# firefly-ice-blue.net
KiCad netlist of a schematic drawn in EAGLE
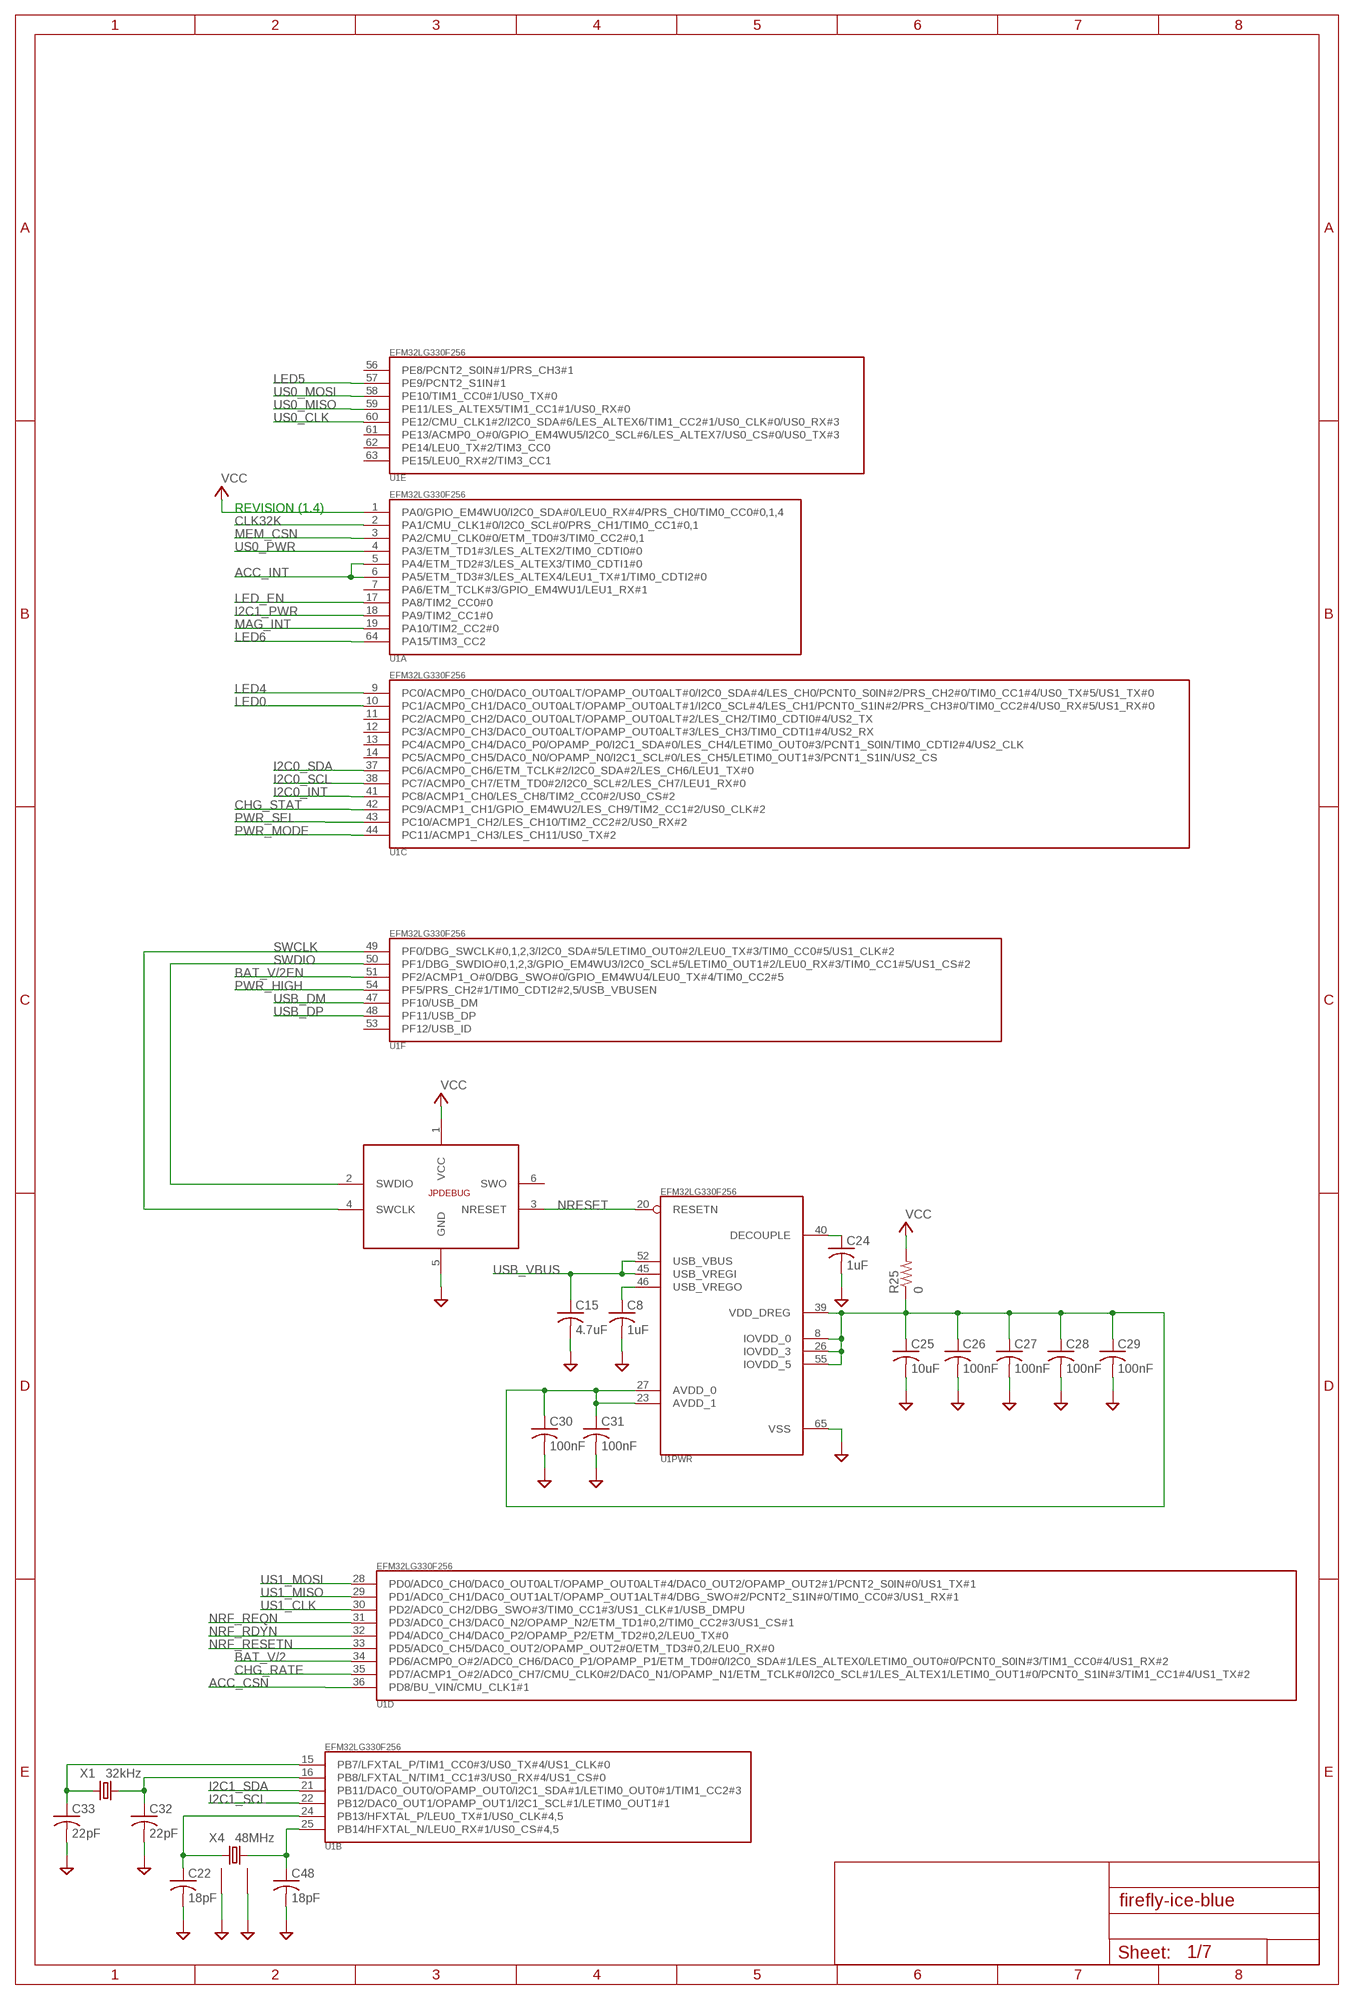
[diagram p0: schematic, sheet 1]
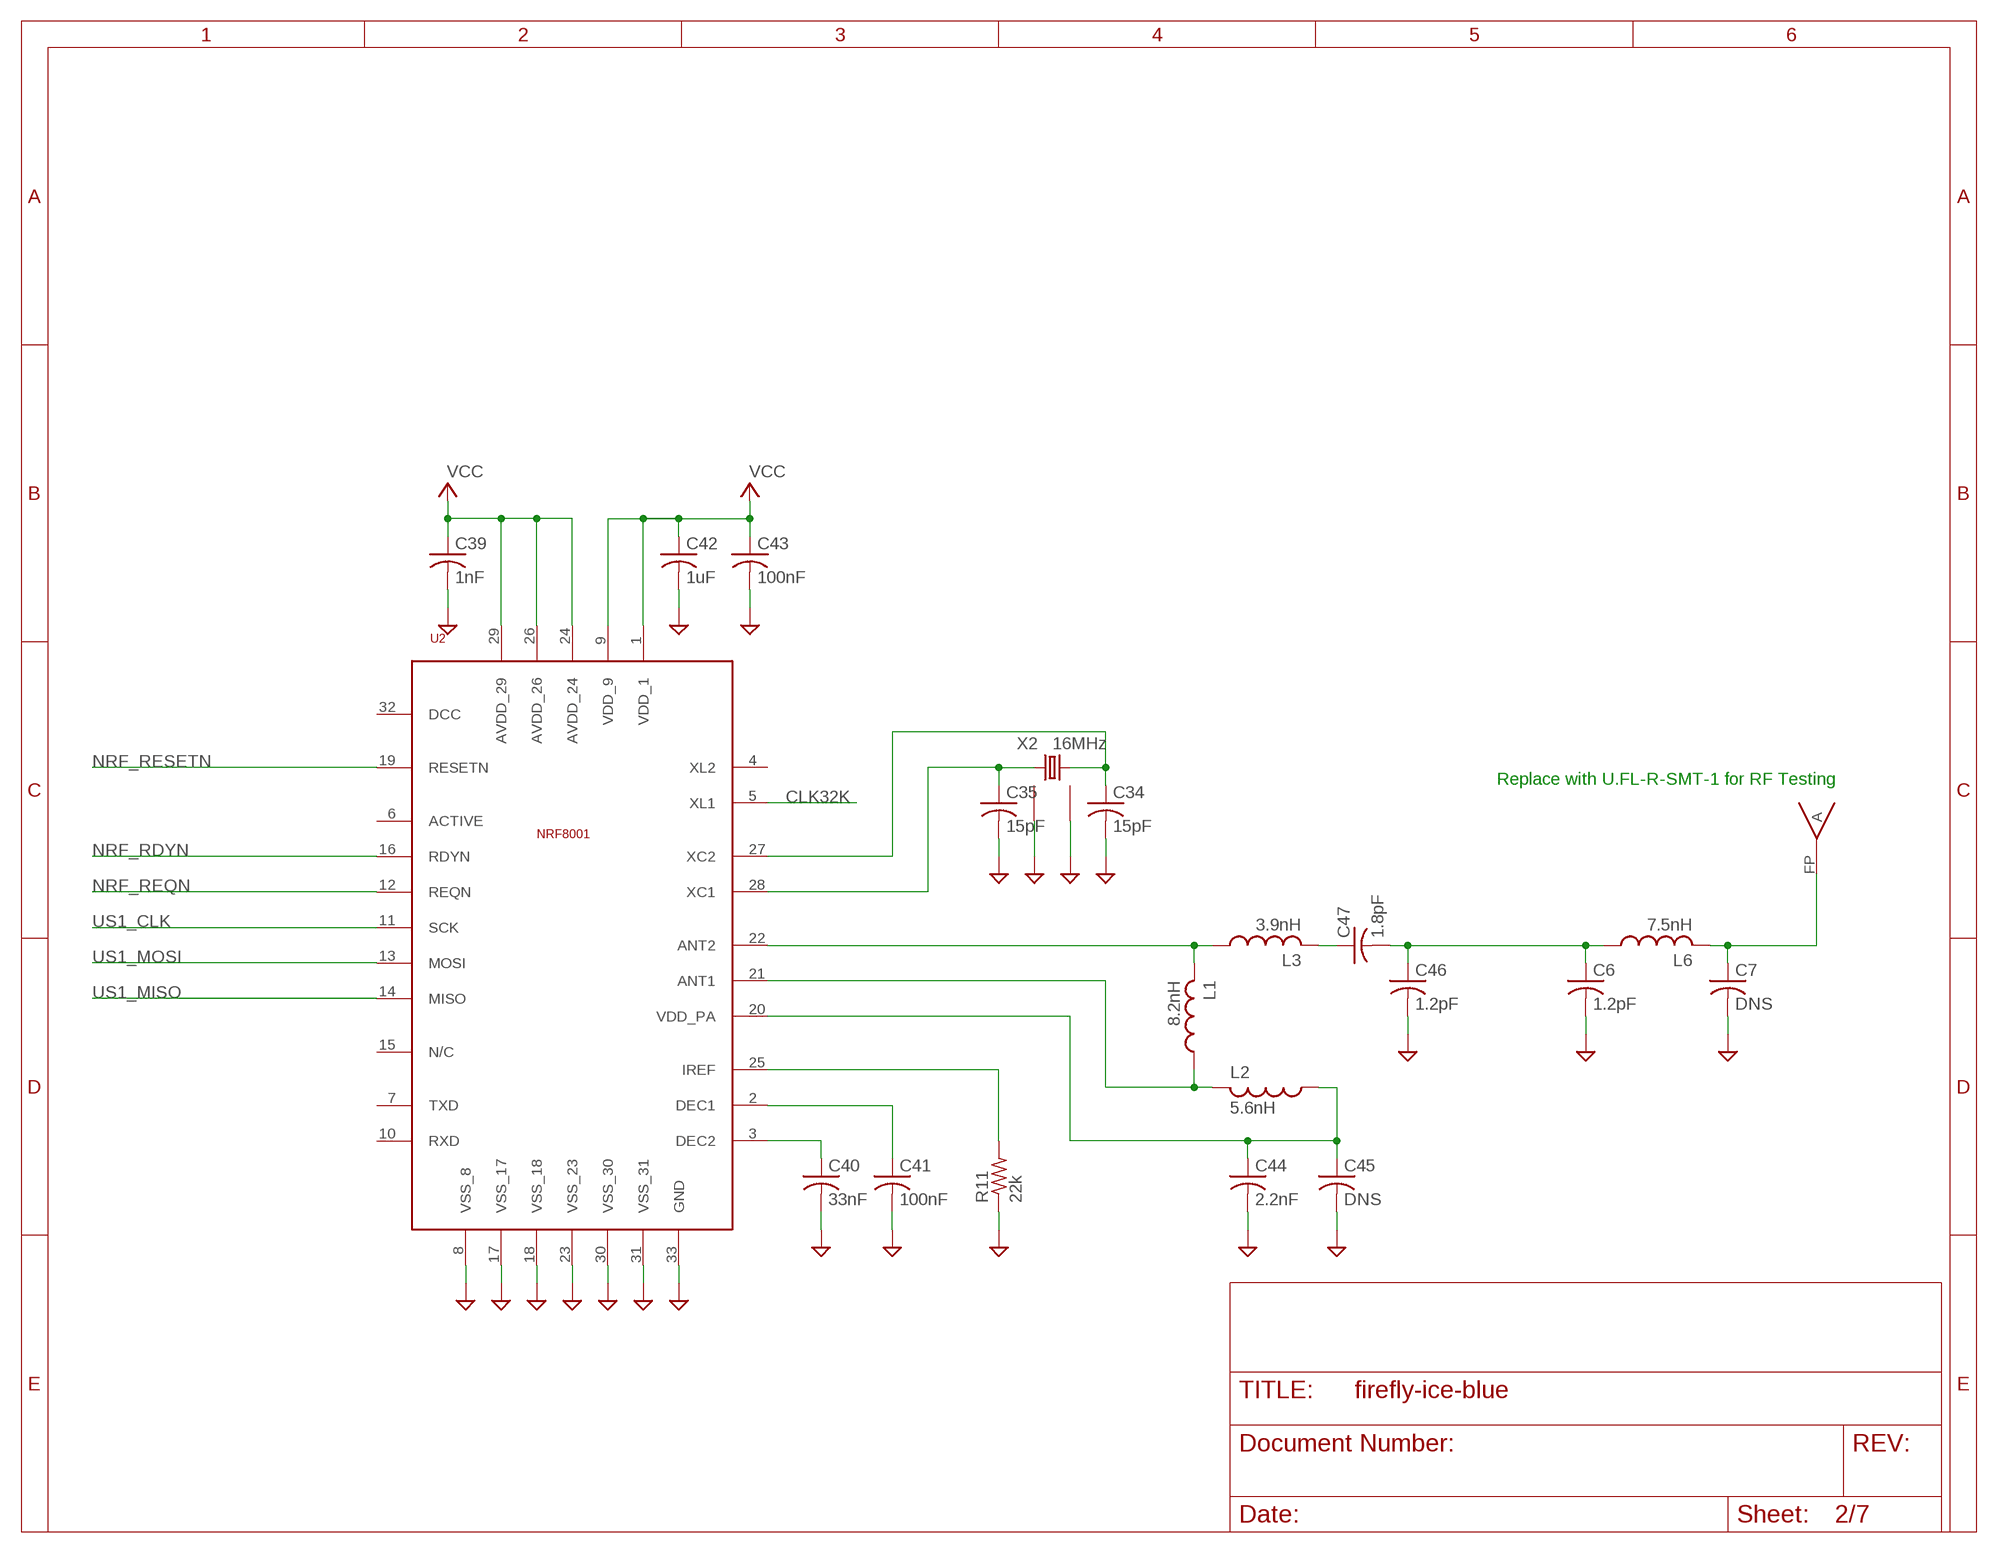
[diagram p1: schematic, sheet 2]
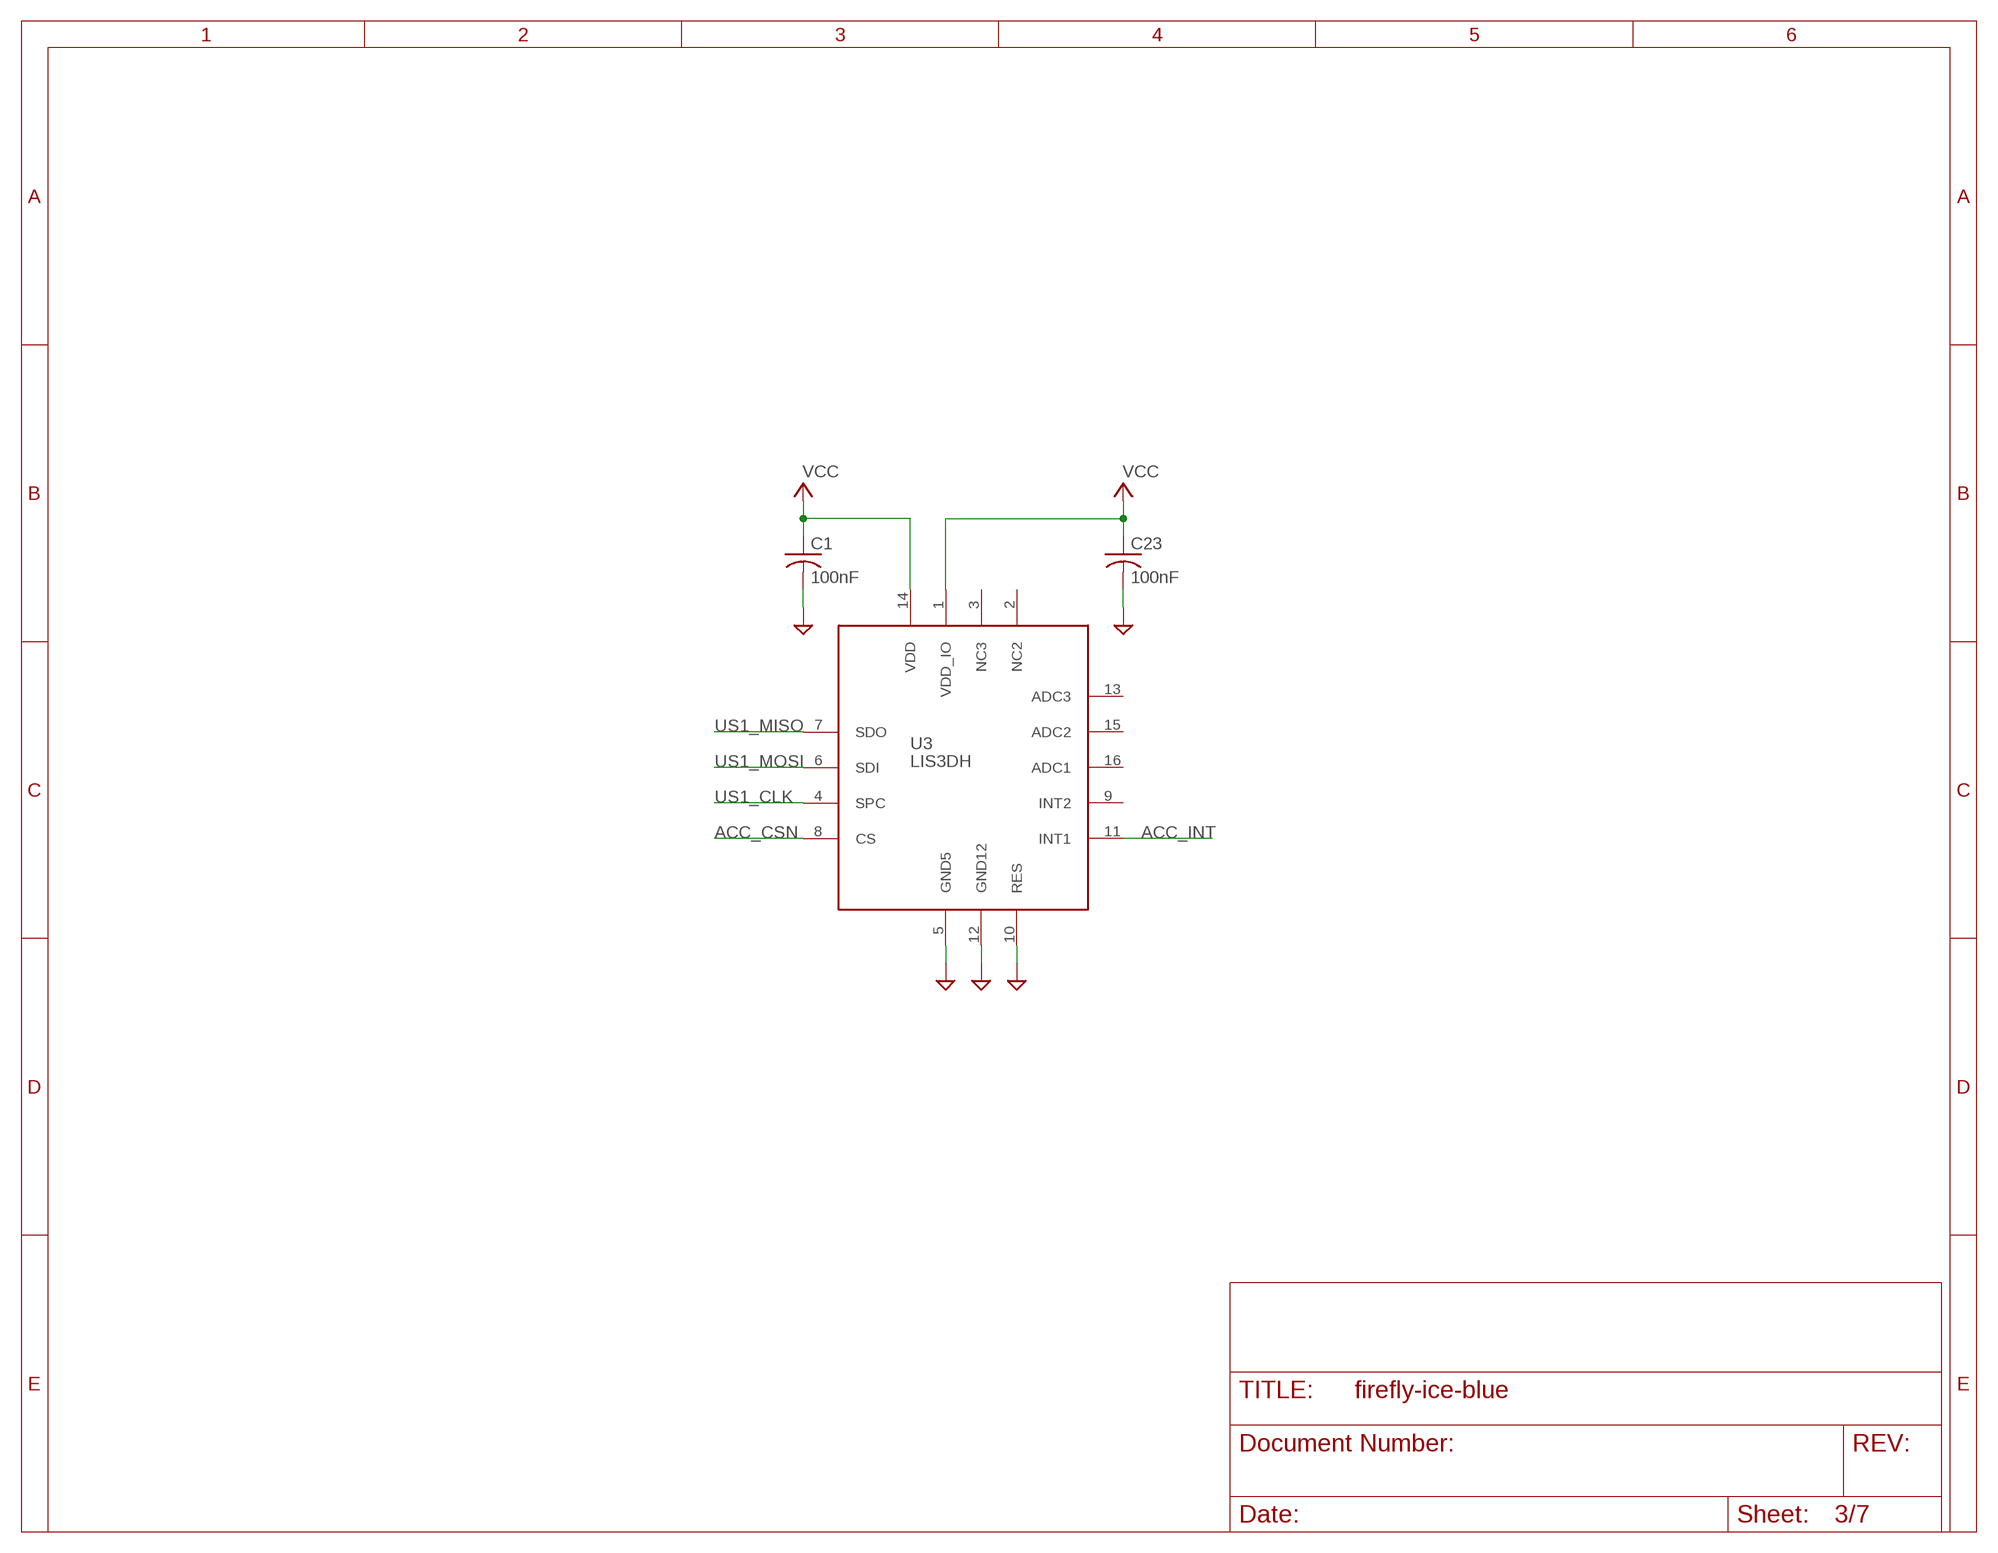
[diagram p2: schematic, sheet 3]
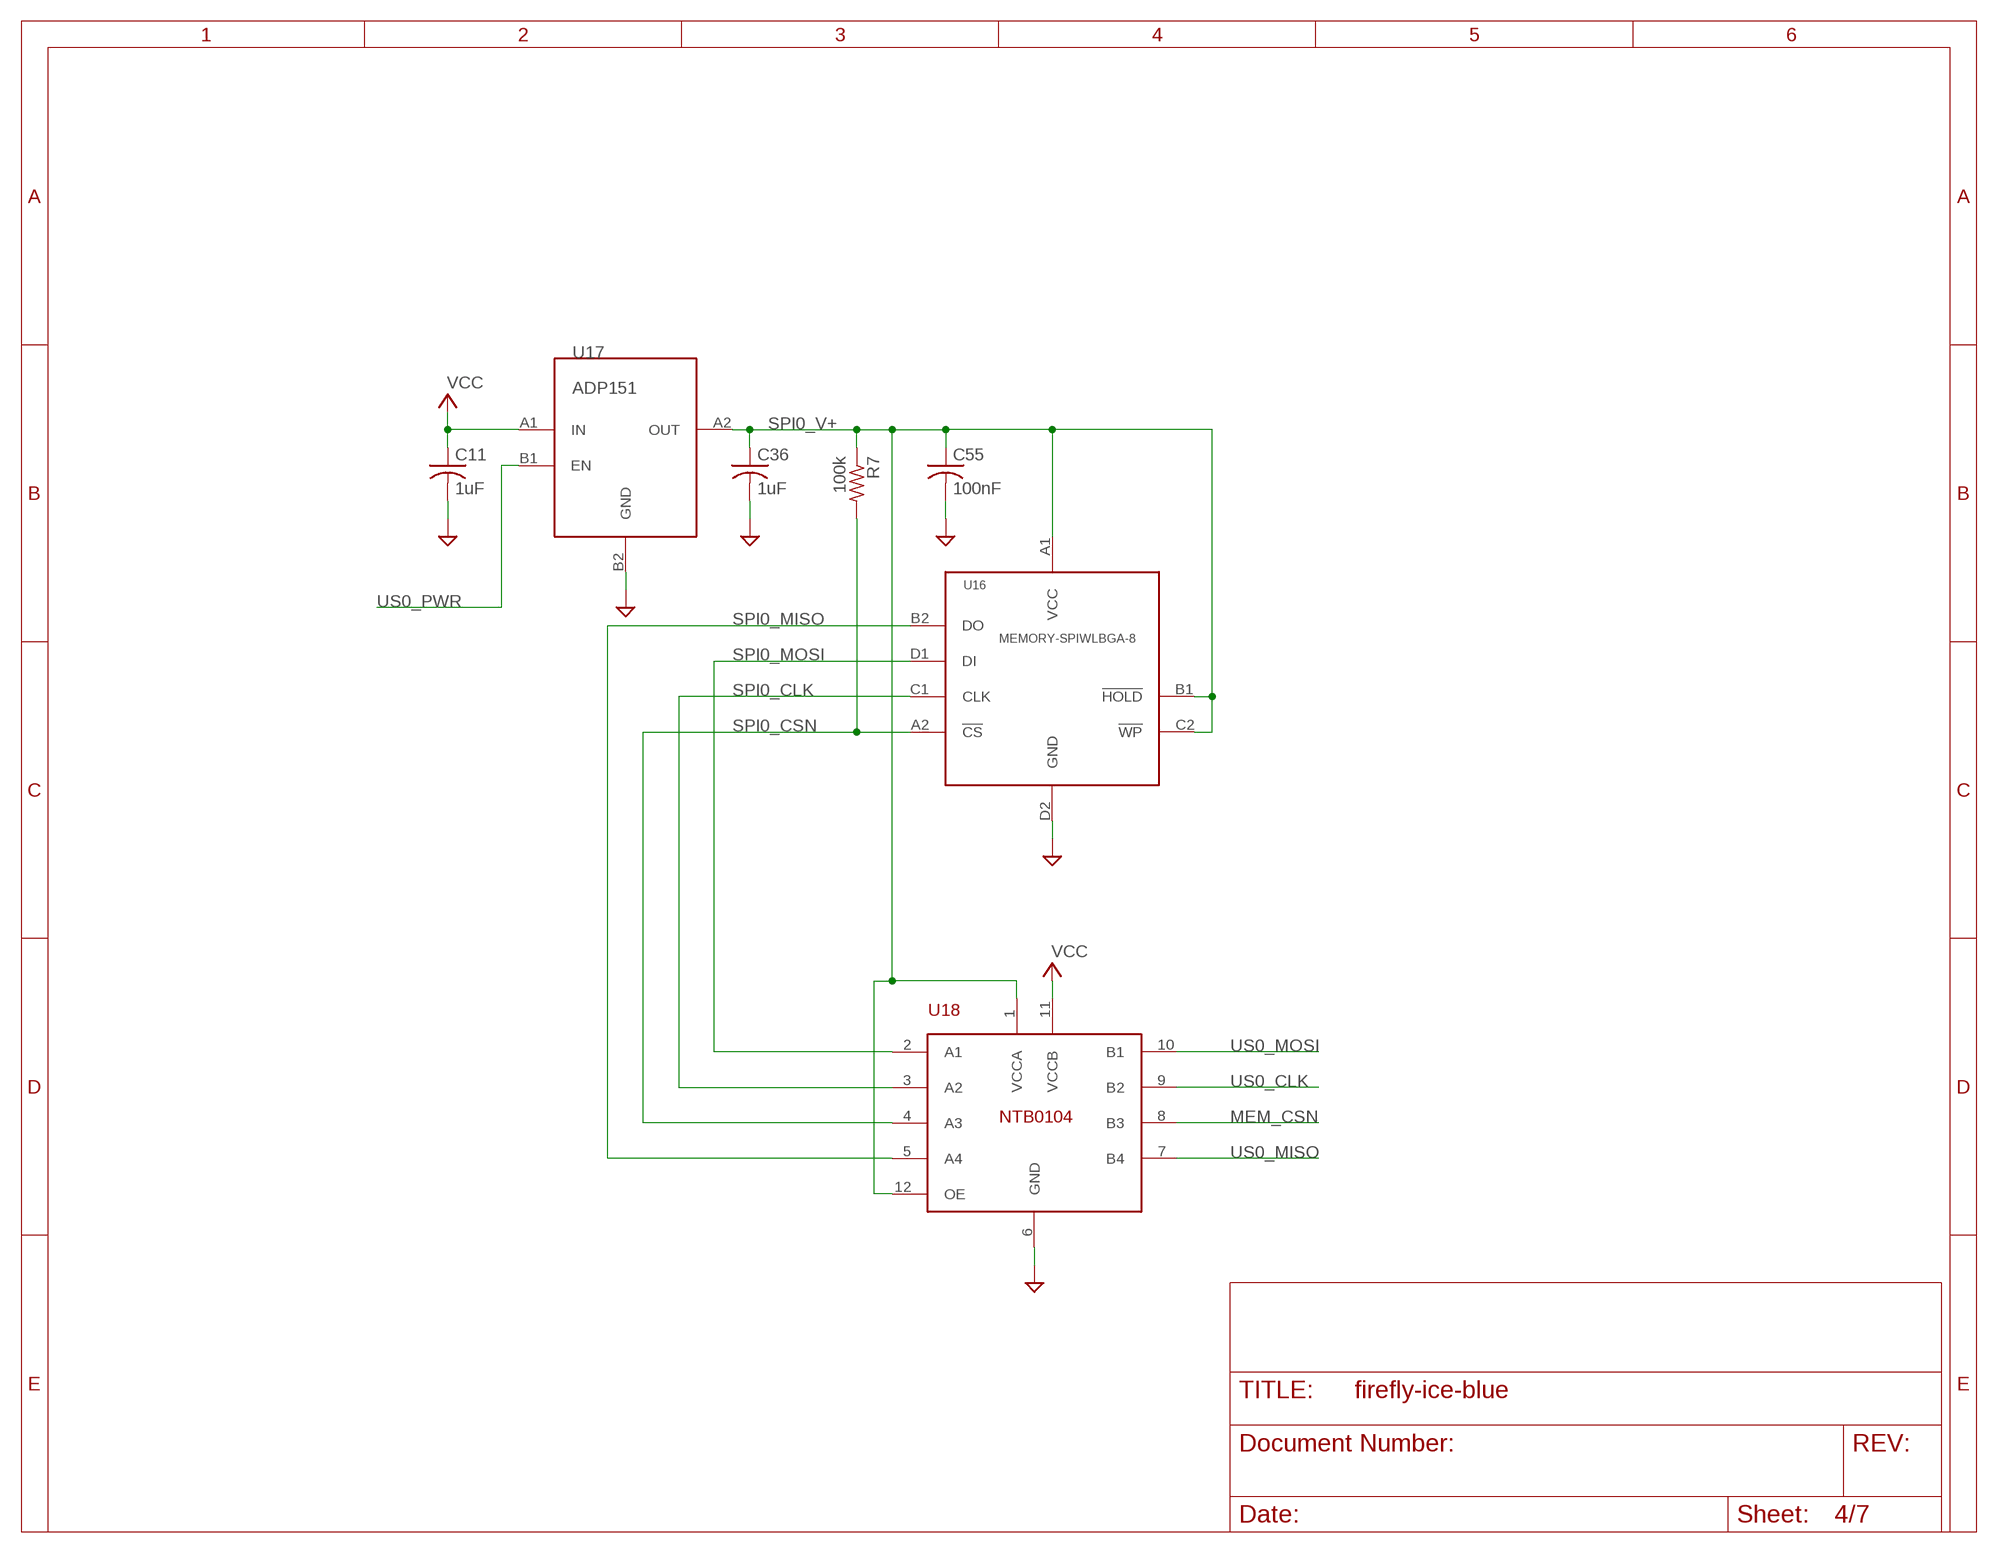
[diagram p3: schematic, sheet 4]
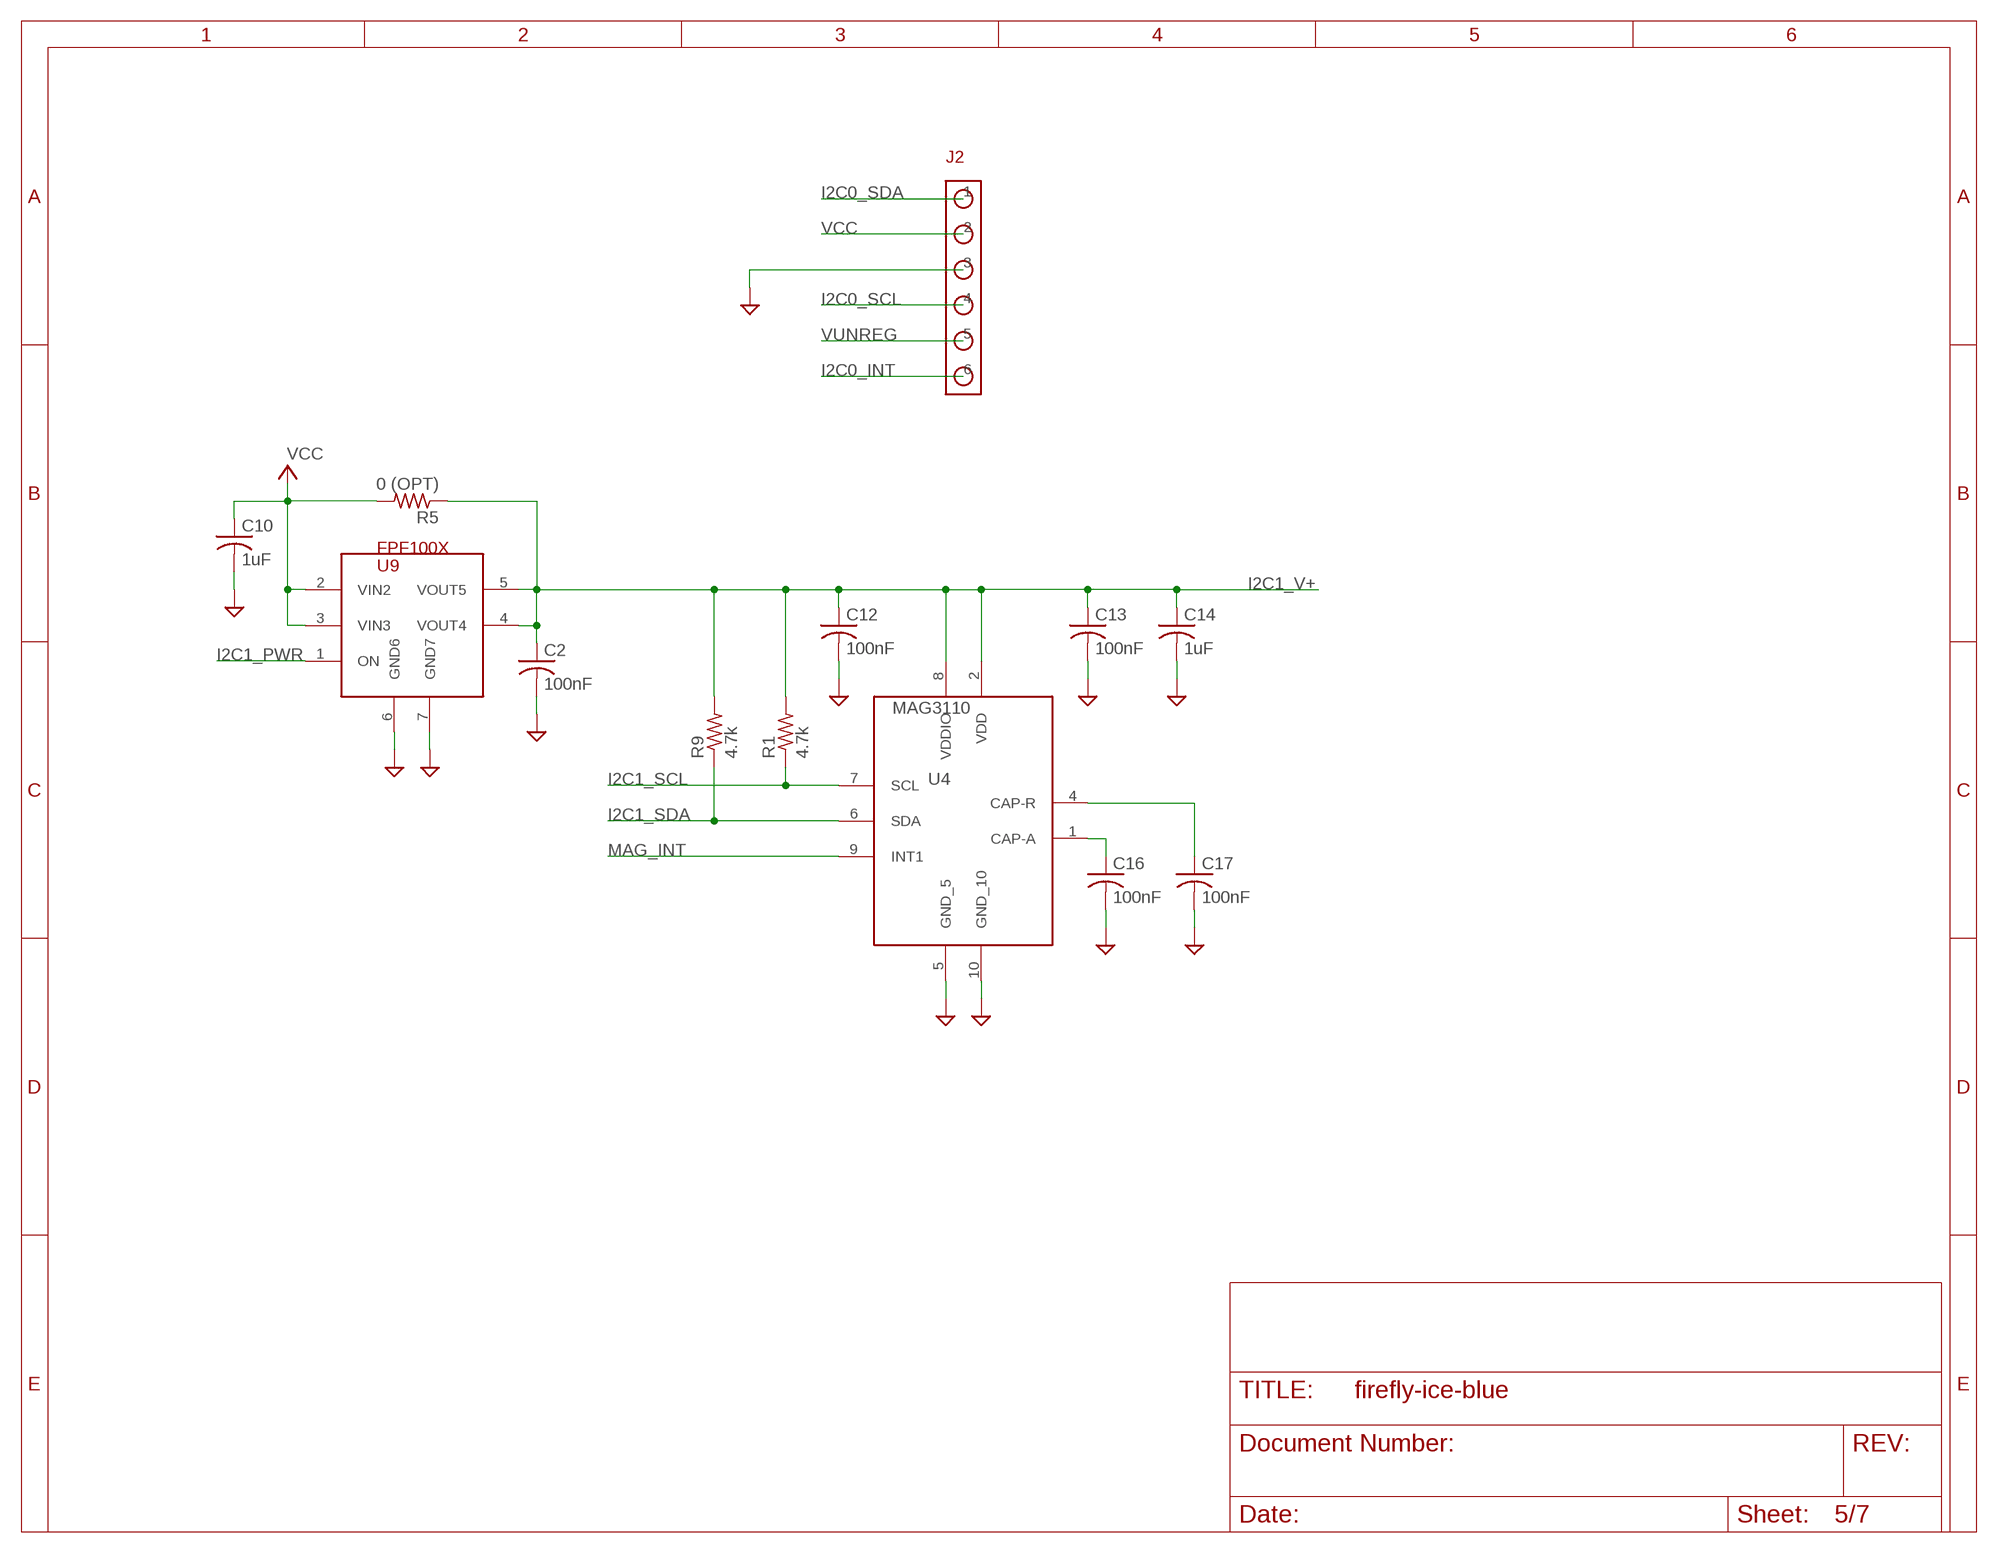
[diagram p4: schematic, sheet 5]
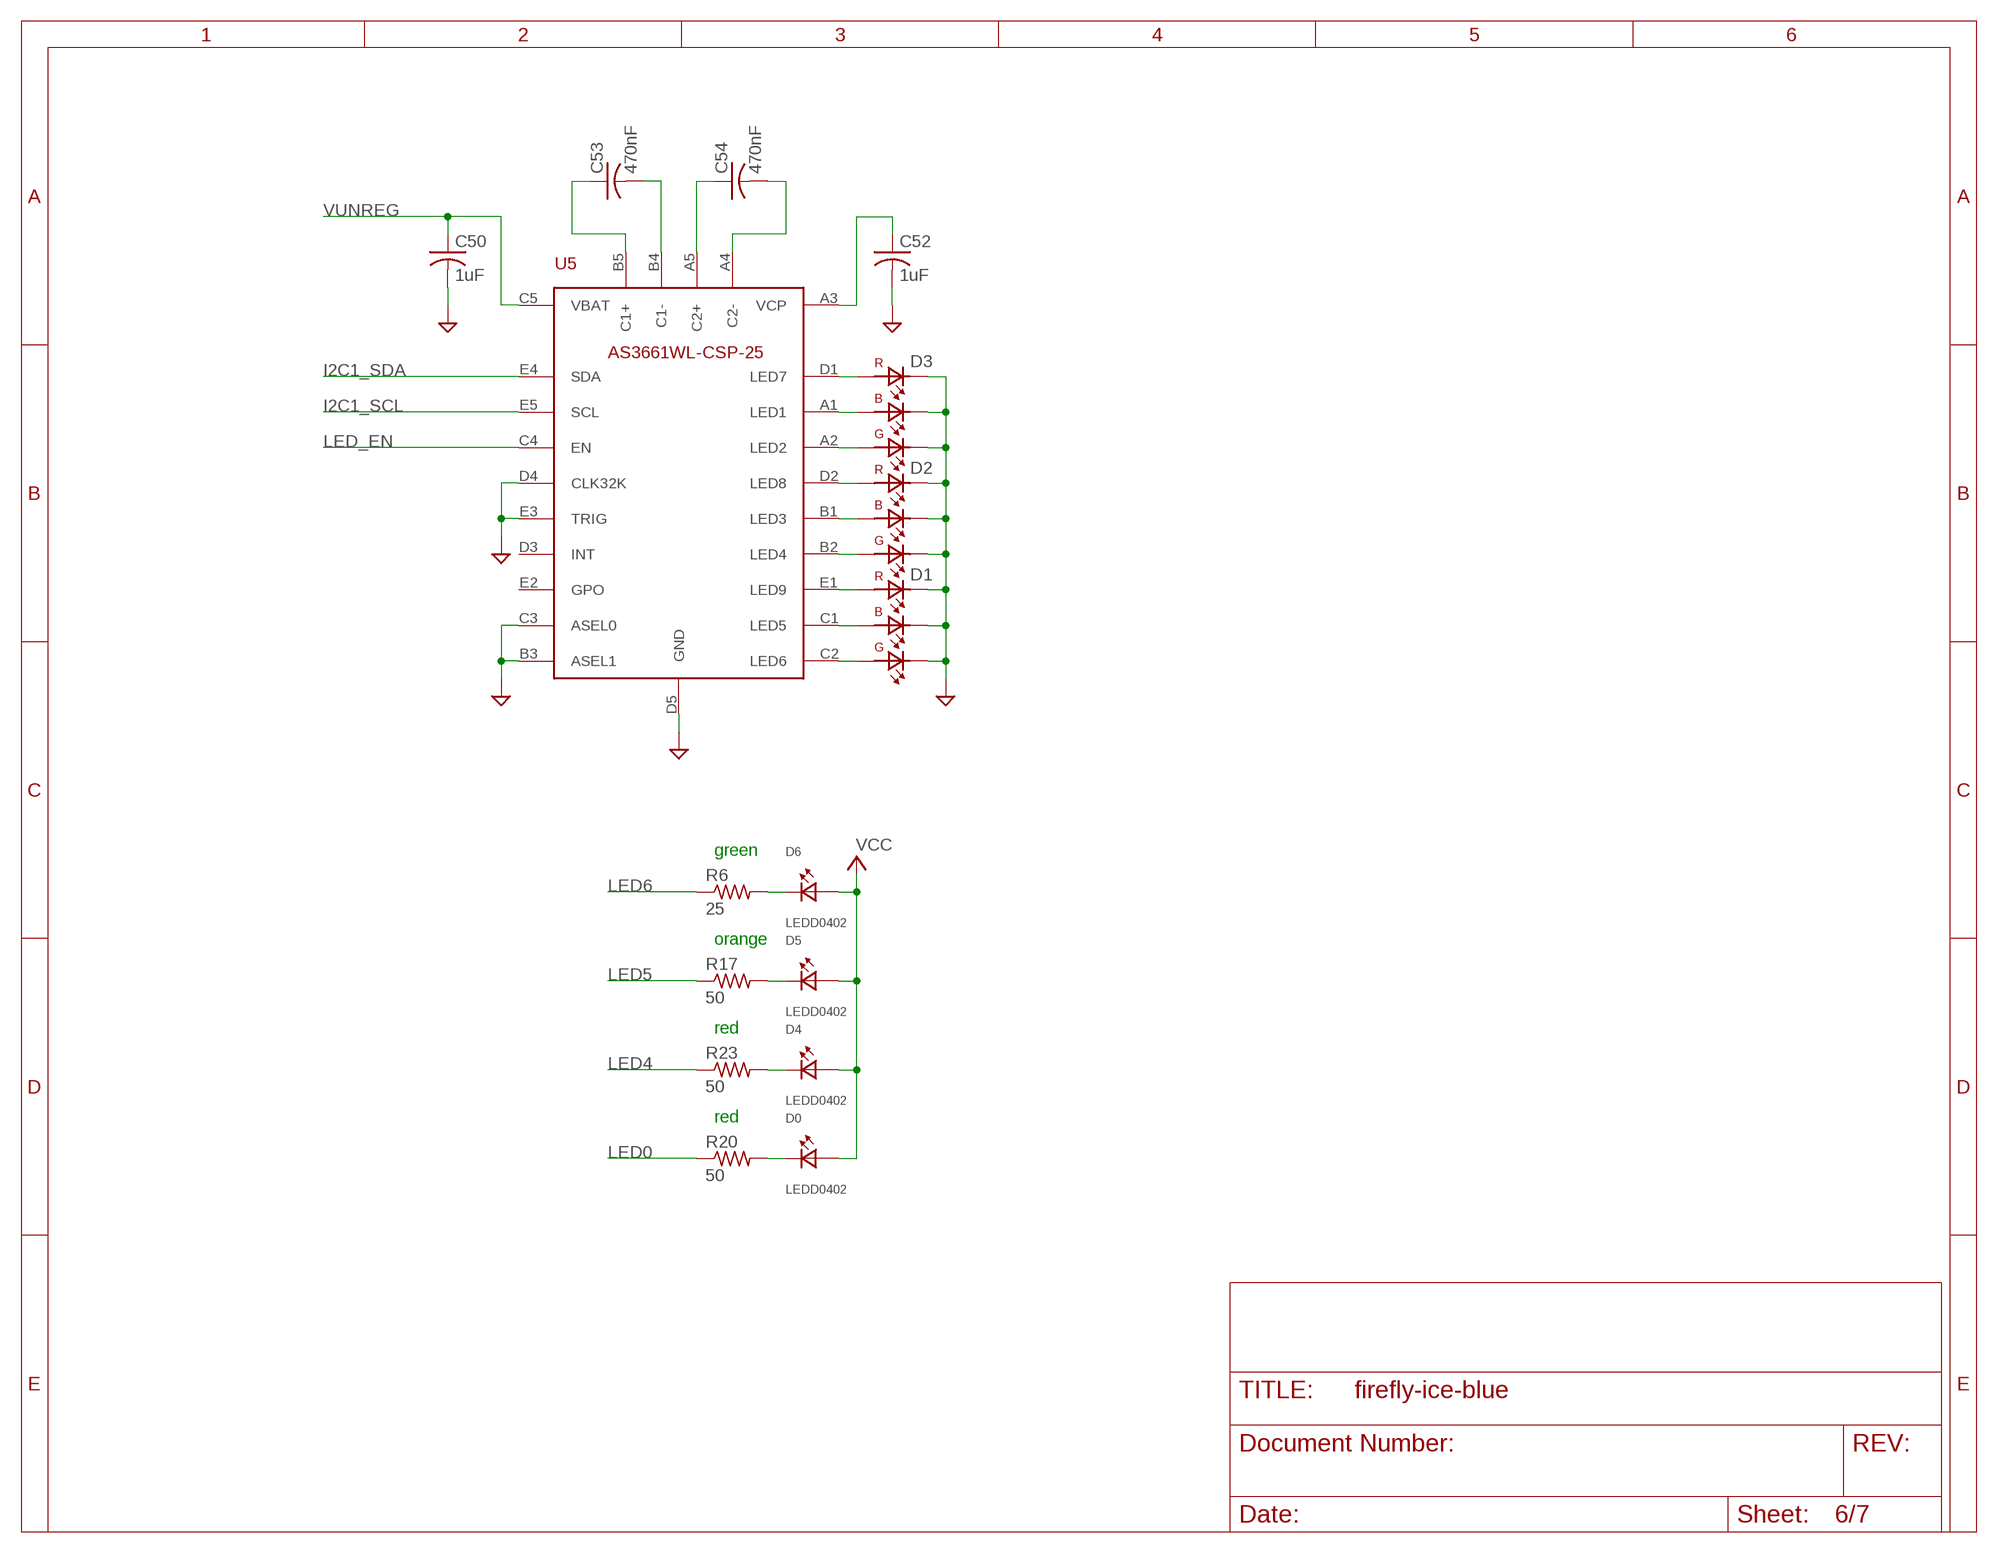
[diagram p5: schematic, sheet 6]
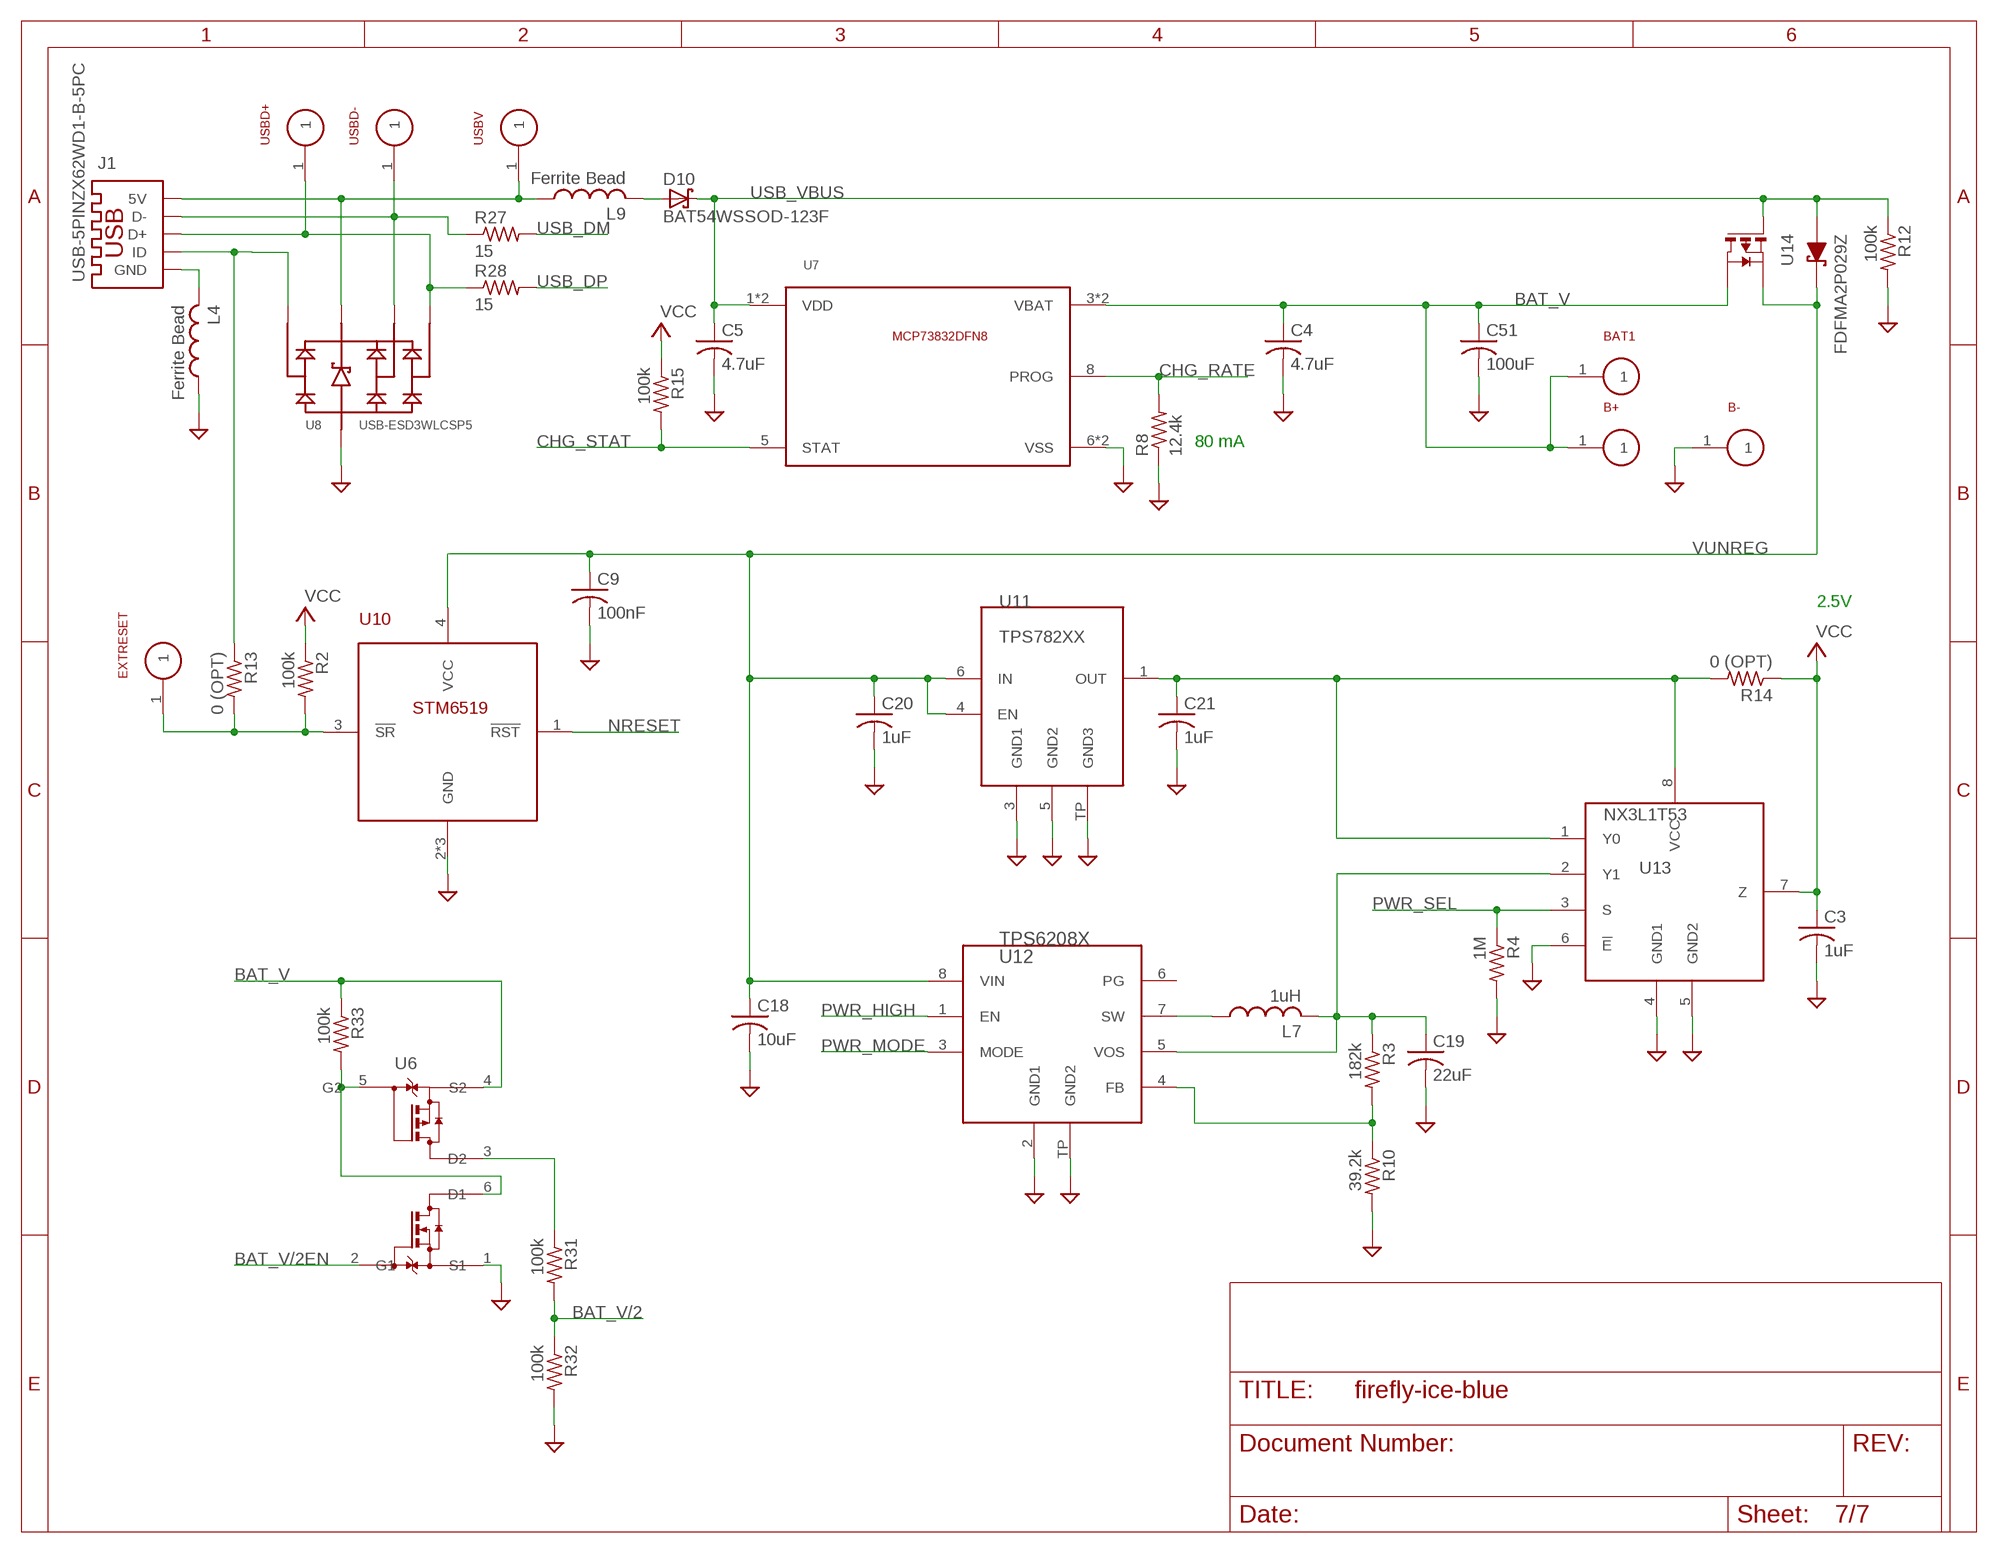
[diagram p6: schematic, sheet 7]

(export (version "E")
  (design (tool "Eeschema 10.0.6"))
  (components
    (comp (ref "C8")
      (value "1uF")
      (footprint "eagle-import:C0201")
      (fields (field (name "MANUFACTURER") "TDK Corporation"))
      (libsource (lib "eagle-import") (part "C-USC0201"))
    )
    (comp (ref "C15")
      (value "4.7uF")
      (footprint "eagle-import:C0402")
      (fields (field (name "MANUFACTURER") "TDK Corporation"))
      (libsource (lib "eagle-import") (part "C-USC0402"))
    )
    (comp (ref "C22")
      (value "18pF")
      (footprint "eagle-import:C0201")
      (fields (field (name "MANUFACTURER") "Johanson Technology Inc"))
      (libsource (lib "eagle-import") (part "C-USC0201"))
    )
    (comp (ref "C24")
      (value "1uF")
      (footprint "eagle-import:C0201")
      (fields (field (name "MANUFACTURER") "TDK Corporation"))
      (libsource (lib "eagle-import") (part "C-USC0201"))
    )
    (comp (ref "C25")
      (value "10uF")
      (footprint "eagle-import:C0402")
      (fields (field (name "MANUFACTURER") "Samsung Electro-Mechanics America, Inc"))
      (libsource (lib "eagle-import") (part "C-USC0402"))
    )
    (comp (ref "C26")
      (value "100nF")
      (footprint "eagle-import:C0201")
      (fields (field (name "MANUFACTURER") "Murata"))
      (libsource (lib "eagle-import") (part "C-USC0201"))
    )
    (comp (ref "C27")
      (value "100nF")
      (footprint "eagle-import:C0201")
      (fields (field (name "MANUFACTURER") "Murata"))
      (libsource (lib "eagle-import") (part "C-USC0201"))
    )
    (comp (ref "C28")
      (value "100nF")
      (footprint "eagle-import:C0201")
      (fields (field (name "MANUFACTURER") "Murata"))
      (libsource (lib "eagle-import") (part "C-USC0201"))
    )
    (comp (ref "C29")
      (value "100nF")
      (footprint "eagle-import:C0201")
      (fields (field (name "MANUFACTURER") "Murata"))
      (libsource (lib "eagle-import") (part "C-USC0201"))
    )
    (comp (ref "C30")
      (value "100nF")
      (footprint "eagle-import:C0201")
      (fields (field (name "MANUFACTURER") "Murata"))
      (libsource (lib "eagle-import") (part "C-USC0201"))
    )
    (comp (ref "C31")
      (value "100nF")
      (footprint "eagle-import:C0201")
      (fields (field (name "MANUFACTURER") "Murata"))
      (libsource (lib "eagle-import") (part "C-USC0201"))
    )
    (comp (ref "C32")
      (value "22pF")
      (footprint "eagle-import:C0201")
      (fields (field (name "MANUFACTURER") "AVX Corporation"))
      (libsource (lib "eagle-import") (part "C-USC0201"))
    )
    (comp (ref "C33")
      (value "22pF")
      (footprint "eagle-import:C0201")
      (fields (field (name "MANUFACTURER") "AVX Corporation"))
      (libsource (lib "eagle-import") (part "C-USC0201"))
    )
    (comp (ref "C48")
      (value "18pF")
      (footprint "eagle-import:C0201")
      (fields (field (name "MANUFACTURER") "Johanson Technology Inc"))
      (libsource (lib "eagle-import") (part "C-USC0201"))
    )
    (comp (ref "JPDEBUG")
      (value "TC2030-SWD")
      (footprint "eagle-import:TC2030-MCP-NL")
      (libsource (lib "eagle-import") (part "TC2030-SWD"))
    )
    (comp (ref "R25")
      (value "0")
      (footprint "eagle-import:R0201")
      (fields (field (name "MANUFACTURER") "Panasonic Electronic Components"))
      (libsource (lib "eagle-import") (part "R-US_R0201"))
    )
    (comp (ref "U1")
      (value "EFM32LG330F256")
      (footprint "eagle-import:QFN64")
      (fields
        (field (name "MANUFACTURER") "Energy Micro")
        (field (name "ORDERING-CODE") "EFM32LG330F256-QFN64")
      )
      (libsource (lib "eagle-import") (part "EFM32LG330F256"))
    )
    (comp (ref "X1")
      (value "32kHz")
      (footprint "eagle-import:9HT10")
      (fields (field (name "MANUFACTURER") "AVX Corp/Kyocera Corp"))
      (libsource (lib "eagle-import") (part "XTAL29HT10"))
    )
    (comp (ref "X4")
      (value "48MHz")
      (footprint "eagle-import:ABM11")
      (fields (field (name "MANUFACTURER") "Abracon Corporation"))
      (libsource (lib "eagle-import") (part "XTALABM11"))
    )
    (comp (ref "C11")
      (value "1uF")
      (footprint "eagle-import:C0201")
      (fields (field (name "MANUFACTURER") "TDK Corporation"))
      (libsource (lib "eagle-import") (part "C-USC0201"))
    )
    (comp (ref "C36")
      (value "1uF")
      (footprint "eagle-import:C0201")
      (fields (field (name "MANUFACTURER") "TDK Corporation"))
      (libsource (lib "eagle-import") (part "C-USC0201"))
    )
    (comp (ref "C55")
      (value "100nF")
      (footprint "eagle-import:C0201")
      (fields (field (name "MANUFACTURER") "Murata"))
      (libsource (lib "eagle-import") (part "C-USC0201"))
    )
    (comp (ref "R7")
      (value "100k")
      (footprint "eagle-import:R0201")
      (fields (field (name "MANUFACTURER") "Yageo"))
      (libsource (lib "eagle-import") (part "R-US_R0201"))
    )
    (comp (ref "U16")
      (value "MEMORY-SPIWLBGA-8")
      (footprint "eagle-import:WLBGA-8")
      (fields (field (name "MANUFACTURER") "Winbond"))
      (libsource (lib "eagle-import") (part "MEMORY-SPIWLBGA-8"))
    )
    (comp (ref "U17")
      (value "ADP151")
      (footprint "eagle-import:CB-4-3")
      (fields (field (name "MANUFACTURER") "Analog Devices"))
      (libsource (lib "eagle-import") (part "ADP151"))
    )
    (comp (ref "U18")
      (value "NTB0104")
      (footprint "eagle-import:XQFN12")
      (fields (field (name "MANUFACTURER") "NXP Semiconductors"))
      (libsource (lib "eagle-import") (part "NTB0104"))
    )
    (comp (ref "C2")
      (value "100nF")
      (footprint "eagle-import:C0201")
      (fields (field (name "MANUFACTURER") "Murata"))
      (libsource (lib "eagle-import") (part "C-USC0201"))
    )
    (comp (ref "C10")
      (value "1uF")
      (footprint "eagle-import:C0201")
      (fields (field (name "MANUFACTURER") "TDK Corporation"))
      (libsource (lib "eagle-import") (part "C-USC0201"))
    )
    (comp (ref "C12")
      (value "100nF")
      (footprint "eagle-import:C0201")
      (fields (field (name "MANUFACTURER") "Murata"))
      (libsource (lib "eagle-import") (part "C-USC0201"))
    )
    (comp (ref "C13")
      (value "100nF")
      (footprint "eagle-import:C0201")
      (fields (field (name "MANUFACTURER") "Murata"))
      (libsource (lib "eagle-import") (part "C-USC0201"))
    )
    (comp (ref "C14")
      (value "1uF")
      (footprint "eagle-import:C0201")
      (fields (field (name "MANUFACTURER") "TDK Corporation"))
      (libsource (lib "eagle-import") (part "C-USC0201"))
    )
    (comp (ref "C16")
      (value "100nF")
      (footprint "eagle-import:C0201")
      (fields (field (name "MANUFACTURER") "Murata"))
      (libsource (lib "eagle-import") (part "C-USC0201"))
    )
    (comp (ref "C17")
      (value "100nF")
      (footprint "eagle-import:C0201")
      (fields (field (name "MANUFACTURER") "Murata"))
      (libsource (lib "eagle-import") (part "C-USC0201"))
    )
    (comp (ref "J2")
      (value "CON-6SOCKET")
      (footprint "eagle-import:M40-3100345R")
      (fields (field (name "MANUFACTURER") "Harwin Inc"))
      (libsource (lib "eagle-import") (part "CON-6SOCKET"))
    )
    (comp (ref "R1")
      (value "4.7k")
      (footprint "eagle-import:R0201")
      (fields (field (name "MANUFACTURER") "Panasonic Electronic Components"))
      (libsource (lib "eagle-import") (part "R-US_R0201"))
    )
    (comp (ref "R5")
      (value "0 (OPT)")
      (footprint "eagle-import:R0201")
      (fields (field (name "MANUFACTURER") "Panasonic Electronic Components"))
      (libsource (lib "eagle-import") (part "R-US_R0201"))
    )
    (comp (ref "R9")
      (value "4.7k")
      (footprint "eagle-import:R0201")
      (fields (field (name "MANUFACTURER") "Panasonic Electronic Components"))
      (libsource (lib "eagle-import") (part "R-US_R0201"))
    )
    (comp (ref "U4")
      (value "MAG3110")
      (footprint "eagle-import:DFN10-2X2")
      (fields (field (name "MANUFACTURER") "Freescale Semiconductor"))
      (libsource (lib "eagle-import") (part "MAG3110"))
    )
    (comp (ref "U9")
      (value "FPF100X")
      (footprint "eagle-import:MICROFET-2X2-6L")
      (fields (field (name "MANUFACTURER") "Fairchild Semiconductor"))
      (libsource (lib "eagle-import") (part "FPF100X"))
    )
    (comp (ref "B+")
      (value "TARGET-PINWP-28AWG")
      (footprint "eagle-import:WP-28AWG")
      (libsource (lib "eagle-import") (part "TARGET-PINWP-28AWG"))
    )
    (comp (ref "B-")
      (value "TARGET-PINWP-28AWG")
      (footprint "eagle-import:WP-28AWG")
      (libsource (lib "eagle-import") (part "TARGET-PINWP-28AWG"))
    )
    (comp (ref "BAT1")
      (value "TARGET-PIN")
      (footprint "eagle-import:TARGET-PIN-1MM")
      (libsource (lib "eagle-import") (part "TARGET-PIN"))
    )
    (comp (ref "C3")
      (value "1uF")
      (footprint "eagle-import:C0201")
      (fields (field (name "MANUFACTURER") "TDK Corporation"))
      (libsource (lib "eagle-import") (part "C-USC0201"))
    )
    (comp (ref "C4")
      (value "4.7uF")
      (footprint "eagle-import:C0402")
      (fields (field (name "MANUFACTURER") "TDK Corporation"))
      (libsource (lib "eagle-import") (part "C-USC0402"))
    )
    (comp (ref "C5")
      (value "4.7uF")
      (footprint "eagle-import:C0402")
      (fields (field (name "MANUFACTURER") "TDK Corporation"))
      (libsource (lib "eagle-import") (part "C-USC0402"))
    )
    (comp (ref "C9")
      (value "100nF")
      (footprint "eagle-import:C0201")
      (fields (field (name "MANUFACTURER") "Murata"))
      (libsource (lib "eagle-import") (part "C-USC0201"))
    )
    (comp (ref "C18")
      (value "10uF")
      (footprint "eagle-import:C0402")
      (fields (field (name "MANUFACTURER") "Samsung Electro-Mechanics America, Inc"))
      (libsource (lib "eagle-import") (part "C-USC0402"))
    )
    (comp (ref "C19")
      (value "22uF")
      (footprint "eagle-import:C0603")
      (fields (field (name "MANUFACTURER") "TDK Corporation"))
      (libsource (lib "eagle-import") (part "C-USC0603"))
    )
    (comp (ref "C20")
      (value "1uF")
      (footprint "eagle-import:C0201")
      (fields (field (name "MANUFACTURER") "TDK Corporation"))
      (libsource (lib "eagle-import") (part "C-USC0201"))
    )
    (comp (ref "C21")
      (value "1uF")
      (footprint "eagle-import:C0201")
      (fields (field (name "MANUFACTURER") "TDK Corporation"))
      (libsource (lib "eagle-import") (part "C-USC0201"))
    )
    (comp (ref "C51")
      (value "100uF")
      (footprint "eagle-import:C1206")
      (fields (field (name "MANUFACTURER") "Kemet"))
      (libsource (lib "eagle-import") (part "C-USC1206"))
    )
    (comp (ref "D10")
      (value "BAT54WSSOD-123F")
      (footprint "eagle-import:SOD-123F")
      (fields (field (name "MANUFACTURER") "Rohm Semiconductor"))
      (libsource (lib "eagle-import") (part "BAT54WSSOD-123F"))
    )
    (comp (ref "EXTRESET")
      (value "TARGET-PIN")
      (footprint "eagle-import:TARGET-PIN-1MM")
      (libsource (lib "eagle-import") (part "TARGET-PIN"))
    )
    (comp (ref "J1")
      (value "USB-5PINZX62WD1-B-5PC")
      (footprint "eagle-import:ZX62WD1-B-5PC")
      (fields (field (name "MANUFACTURER") "TE Connectivity"))
      (libsource (lib "eagle-import") (part "USB-5PINZX62WD1-B-5PC"))
    )
    (comp (ref "L4")
      (value "Ferrite Bead")
      (footprint "eagle-import:L0201")
      (fields (field (name "MANUFACTURER") "TDK Corporation"))
      (libsource (lib "eagle-import") (part "L-USL0201"))
    )
    (comp (ref "L7")
      (value "1uH")
      (footprint "eagle-import:L0805")
      (fields (field (name "MANUFACTURER") "WURTH"))
      (libsource (lib "eagle-import") (part "INDUCTORL0805"))
    )
    (comp (ref "L9")
      (value "Ferrite Bead")
      (footprint "eagle-import:L0201")
      (fields (field (name "MANUFACTURER") "TDK Corportation"))
      (libsource (lib "eagle-import") (part "L-USL0201"))
    )
    (comp (ref "R2")
      (value "100k")
      (footprint "eagle-import:R0201")
      (fields (field (name "MANUFACTURER") "Yageo"))
      (libsource (lib "eagle-import") (part "R-US_R0201"))
    )
    (comp (ref "R3")
      (value "182k")
      (footprint "eagle-import:R0201")
      (fields (field (name "MANUFACTURER") "Panasonic Electronic Components"))
      (libsource (lib "eagle-import") (part "R-US_R0201"))
    )
    (comp (ref "R4")
      (value "1M")
      (footprint "eagle-import:R0201")
      (fields (field (name "MANUFACTURER") "Panasonic Electronic Components"))
      (libsource (lib "eagle-import") (part "R-US_R0201"))
    )
    (comp (ref "R8")
      (value "12.4k")
      (footprint "eagle-import:R0201")
      (fields (field (name "MANUFACTURER") "Panasonic Electronic Components"))
      (libsource (lib "eagle-import") (part "R-US_R0201"))
    )
    (comp (ref "R10")
      (value "39.2k")
      (footprint "eagle-import:R0201")
      (fields (field (name "MANUFACTURER") "Panasonic Electronic Components"))
      (libsource (lib "eagle-import") (part "R-US_R0201"))
    )
    (comp (ref "R12")
      (value "100k")
      (footprint "eagle-import:R0201")
      (fields (field (name "MANUFACTURER") "Yageo"))
      (libsource (lib "eagle-import") (part "R-US_R0201"))
    )
    (comp (ref "R13")
      (value "0 (OPT)")
      (footprint "eagle-import:R0201")
      (fields (field (name "MANUFACTURER") "Panasonic Electronic Components"))
      (libsource (lib "eagle-import") (part "R-US_R0201"))
    )
    (comp (ref "R14")
      (value "0 (OPT)")
      (footprint "eagle-import:R0201")
      (fields (field (name "MANUFACTURER") "Panasonic Electronic Components"))
      (libsource (lib "eagle-import") (part "R-US_R0201"))
    )
    (comp (ref "R15")
      (value "100k")
      (footprint "eagle-import:R0201")
      (fields (field (name "MANUFACTURER") "Yageo"))
      (libsource (lib "eagle-import") (part "R-US_R0201"))
    )
    (comp (ref "R27")
      (value "15")
      (footprint "eagle-import:R0201")
      (fields (field (name "MANUFACTURER") "Panasonic Electronic Components"))
      (libsource (lib "eagle-import") (part "R-US_R0201"))
    )
    (comp (ref "R28")
      (value "15")
      (footprint "eagle-import:R0201")
      (fields (field (name "MANUFACTURER") "Panasonic Electronic Components"))
      (libsource (lib "eagle-import") (part "R-US_R0201"))
    )
    (comp (ref "R31")
      (value "100k")
      (footprint "eagle-import:R0201")
      (fields (field (name "MANUFACTURER") "Yageo"))
      (libsource (lib "eagle-import") (part "R-US_R0201"))
    )
    (comp (ref "R32")
      (value "100k")
      (footprint "eagle-import:R0201")
      (fields (field (name "MANUFACTURER") "Yageo"))
      (libsource (lib "eagle-import") (part "R-US_R0201"))
    )
    (comp (ref "R33")
      (value "100k")
      (footprint "eagle-import:R0201")
      (fields (field (name "MANUFACTURER") "Yageo"))
      (libsource (lib "eagle-import") (part "R-US_R0201"))
    )
    (comp (ref "U6")
      (value "MOSFET-N+PSOT963")
      (footprint "eagle-import:SOT963")
      (fields (field (name "MANUFACTURER") "Diodes Inc"))
      (libsource (lib "eagle-import") (part "MOSFET-N+PSOT963"))
    )
    (comp (ref "U7")
      (value "MCP73832DFN8")
      (footprint "eagle-import:DFN8")
      (fields (field (name "MANUFACTURER") "Microchip"))
      (libsource (lib "eagle-import") (part "MCP73832DFN8"))
    )
    (comp (ref "U8")
      (value "USB-ESD3WLCSP5")
      (footprint "eagle-import:WLCSP5")
      (fields (field (name "MANUFACTURER") "NXP Semiconductors"))
      (libsource (lib "eagle-import") (part "USB-ESD3WLCSP5"))
    )
    (comp (ref "U10")
      (value "STM6519")
      (footprint "eagle-import:UDFN6")
      (fields (field (name "MANUFACTURER") "STMicroelectronics"))
      (libsource (lib "eagle-import") (part "STM6519"))
    )
    (comp (ref "U11")
      (value "TPS782XX")
      (footprint "eagle-import:S-PWSON-N6")
      (fields (field (name "MANUFACTURER") "Texas Instruments"))
      (libsource (lib "eagle-import") (part "TPS782XX"))
    )
    (comp (ref "U12")
      (value "TPS6208X")
      (footprint "eagle-import:S-PWSON-N8")
      (fields (field (name "MANUFACTURER") "Texas Instruments"))
      (libsource (lib "eagle-import") (part "TPS6208X"))
    )
    (comp (ref "U13")
      (value "NX3L1T53")
      (footprint "eagle-import:SOT902-2")
      (fields (field (name "MANUFACTURER") "NXP Semiconductor"))
      (libsource (lib "eagle-import") (part "NX3L1T53"))
    )
    (comp (ref "U14")
      (value "FDFMA2P029Z")
      (footprint "eagle-import:MO-229")
      (fields (field (name "MANUFACTURER") "Fairchild Semiconductor"))
      (libsource (lib "eagle-import") (part "FDFMA2P029Z"))
    )
    (comp (ref "USBD+")
      (value "TARGET-PIN")
      (footprint "eagle-import:TARGET-PIN-1MM")
      (libsource (lib "eagle-import") (part "TARGET-PIN"))
    )
    (comp (ref "USBD-")
      (value "TARGET-PIN")
      (footprint "eagle-import:TARGET-PIN-1MM")
      (libsource (lib "eagle-import") (part "TARGET-PIN"))
    )
    (comp (ref "USBV")
      (value "TARGET-PIN")
      (footprint "eagle-import:TARGET-PIN-1MM")
      (libsource (lib "eagle-import") (part "TARGET-PIN"))
    )
    (comp (ref "C1")
      (value "100nF")
      (footprint "eagle-import:C0201")
      (fields (field (name "MANUFACTURER") "Murata"))
      (libsource (lib "eagle-import") (part "C-USC0201"))
    )
    (comp (ref "C23")
      (value "100nF")
      (footprint "eagle-import:C0201")
      (fields (field (name "MANUFACTURER") "Murata"))
      (libsource (lib "eagle-import") (part "C-USC0201"))
    )
    (comp (ref "U3")
      (value "LIS3DH")
      (footprint "eagle-import:LGA16_3X3")
      (fields (field (name "MANUFACTURER") "ST"))
      (libsource (lib "eagle-import") (part "LIS3DH"))
    )
    (comp (ref "A1")
      (value "FR05_S1_N_0_110")
      (footprint "eagle-import:FR05_S1_N_0_110")
      (fields (field (name "MANUFACTURER") "Fractus"))
      (libsource (lib "eagle-import") (part "FR05_S1_N_0_110"))
    )
    (comp (ref "C6")
      (value "1.2pF")
      (footprint "eagle-import:C0201")
      (fields (field (name "MANUFACTURER") "TDK"))
      (libsource (lib "eagle-import") (part "C-USC0201"))
    )
    (comp (ref "C7")
      (value "DNS")
      (footprint "eagle-import:C0201")
      (libsource (lib "eagle-import") (part "C-USC0201"))
    )
    (comp (ref "C34")
      (value "15pF")
      (footprint "eagle-import:C0201")
      (fields (field (name "MANUFACTURER") "Johanson Technology Inc"))
      (libsource (lib "eagle-import") (part "C-USC0201"))
    )
    (comp (ref "C35")
      (value "15pF")
      (footprint "eagle-import:C0201")
      (fields (field (name "MANUFACTURER") "Johanson Technology Inc"))
      (libsource (lib "eagle-import") (part "C-USC0201"))
    )
    (comp (ref "C39")
      (value "1nF")
      (footprint "eagle-import:C0201")
      (fields (field (name "MANUFACTURER") "Murata"))
      (libsource (lib "eagle-import") (part "C-USC0201"))
    )
    (comp (ref "C40")
      (value "33nF")
      (footprint "eagle-import:C0201")
      (fields (field (name "MANUFACTURER") "Murata"))
      (libsource (lib "eagle-import") (part "C-USC0201"))
    )
    (comp (ref "C41")
      (value "100nF")
      (footprint "eagle-import:C0201")
      (fields (field (name "MANUFACTURER") "Kemet"))
      (libsource (lib "eagle-import") (part "C-USC0201"))
    )
    (comp (ref "C42")
      (value "1uF")
      (footprint "eagle-import:C0201")
      (fields (field (name "MANUFACTURER") "TDK Corporation"))
      (libsource (lib "eagle-import") (part "C-USC0201"))
    )
    (comp (ref "C43")
      (value "100nF")
      (footprint "eagle-import:C0201")
      (fields (field (name "MANUFACTURER") "Murata"))
      (libsource (lib "eagle-import") (part "C-USC0201"))
    )
    (comp (ref "C44")
      (value "2.2nF")
      (footprint "eagle-import:C0201")
      (fields (field (name "MANUFACTURER") "TDK"))
      (libsource (lib "eagle-import") (part "C-USC0201"))
    )
    (comp (ref "C45")
      (value "DNS")
      (footprint "eagle-import:C0201")
      (libsource (lib "eagle-import") (part "C-USC0201"))
    )
    (comp (ref "C46")
      (value "1.2pF")
      (footprint "eagle-import:C0201")
      (fields (field (name "MANUFACTURER") "TDK"))
      (libsource (lib "eagle-import") (part "C-USC0201"))
    )
    (comp (ref "C47")
      (value "1.8pF")
      (footprint "eagle-import:C0201")
      (fields (field (name "MANUFACTURER") "TDK"))
      (libsource (lib "eagle-import") (part "C-USC0201"))
    )
    (comp (ref "L1")
      (value "8.2nH")
      (footprint "eagle-import:L0201")
      (fields (field (name "MANUFACTURER") "TDK"))
      (libsource (lib "eagle-import") (part "L-USL0201"))
    )
    (comp (ref "L2")
      (value "5.6nH")
      (footprint "eagle-import:L0201")
      (fields (field (name "MANUFACTURER") "TDK"))
      (libsource (lib "eagle-import") (part "L-USL0201"))
    )
    (comp (ref "L3")
      (value "3.9nH")
      (footprint "eagle-import:L0201")
      (fields (field (name "MANUFACTURER") "TDK"))
      (libsource (lib "eagle-import") (part "L-USL0201"))
    )
    (comp (ref "L6")
      (value "7.5nH")
      (footprint "eagle-import:L0201")
      (fields (field (name "MANUFACTURER") "Taiyo Yuden"))
      (libsource (lib "eagle-import") (part "L-USL0201"))
    )
    (comp (ref "R11")
      (value "22k")
      (footprint "eagle-import:R0201")
      (fields (field (name "MANUFACTURER") "Panasonic"))
      (libsource (lib "eagle-import") (part "R-US_R0201"))
    )
    (comp (ref "U2")
      (value "NRF8001")
      (footprint "eagle-import:QFN-32")
      (fields (field (name "MANUFACTURER") "Nordic Semiconductor"))
      (libsource (lib "eagle-import") (part "NRF8001"))
    )
    (comp (ref "X2")
      (value "16MHz")
      (footprint "eagle-import:XTAL2520")
      (fields (field (name "MANUFACTURER") "TXC CORPORATION"))
      (libsource (lib "eagle-import") (part "XTALXTAL2520"))
    )
    (comp (ref "C50")
      (value "1uF")
      (footprint "eagle-import:C0201")
      (fields (field (name "MANUFACTURER") "TDK Corporation"))
      (libsource (lib "eagle-import") (part "C-USC0201"))
    )
    (comp (ref "C52")
      (value "1uF")
      (footprint "eagle-import:C0201")
      (fields (field (name "MANUFACTURER") "TDK Corporation"))
      (libsource (lib "eagle-import") (part "C-USC0201"))
    )
    (comp (ref "C53")
      (value "470nF")
      (footprint "eagle-import:C0201")
      (fields (field (name "MANUFACTURER") "TDK Corporation"))
      (libsource (lib "eagle-import") (part "C-USC0201"))
    )
    (comp (ref "C54")
      (value "470nF")
      (footprint "eagle-import:C0201")
      (fields (field (name "MANUFACTURER") "TDK Corporation"))
      (libsource (lib "eagle-import") (part "C-USC0201"))
    )
    (comp (ref "D0")
      (value "LEDD0402")
      (footprint "eagle-import:D0402")
      (fields (field (name "MANUFACTURER") "Rohm Semiconductor"))
      (libsource (lib "eagle-import") (part "LEDD0402"))
    )
    (comp (ref "D1")
      (value "LED-RGB")
      (footprint "eagle-import:SMLP36")
      (fields (field (name "MANUFACTURER") "Rohm Semiconductor"))
      (libsource (lib "eagle-import") (part "LED-RGB"))
    )
    (comp (ref "D2")
      (value "LED-RGB")
      (footprint "eagle-import:SMLP36")
      (fields (field (name "MANUFACTURER") "Rohm Semiconductor"))
      (libsource (lib "eagle-import") (part "LED-RGB"))
    )
    (comp (ref "D3")
      (value "LED-RGB")
      (footprint "eagle-import:SMLP36")
      (fields (field (name "MANUFACTURER") "Rohm Semiconductor"))
      (libsource (lib "eagle-import") (part "LED-RGB"))
    )
    (comp (ref "D4")
      (value "LEDD0402")
      (footprint "eagle-import:D0402")
      (fields (field (name "MANUFACTURER") "Rohm Semiconductor"))
      (libsource (lib "eagle-import") (part "LEDD0402"))
    )
    (comp (ref "D5")
      (value "LEDD0402")
      (footprint "eagle-import:D0402")
      (fields (field (name "MANUFACTURER") "Panasonic Electronic Components"))
      (libsource (lib "eagle-import") (part "LEDD0402"))
    )
    (comp (ref "D6")
      (value "LEDD0402")
      (footprint "eagle-import:D0402")
      (fields (field (name "MANUFACTURER") "Panasonic Electronic Components"))
      (libsource (lib "eagle-import") (part "LEDD0402"))
    )
    (comp (ref "R6")
      (value "25")
      (footprint "eagle-import:R0201")
      (fields (field (name "MANUFACTURER") "Panasonic Electronic Components"))
      (libsource (lib "eagle-import") (part "R-US_R0201"))
    )
    (comp (ref "R17")
      (value "50")
      (footprint "eagle-import:R0201")
      (fields (field (name "MANUFACTURER") "Panasonic Electronic Components"))
      (libsource (lib "eagle-import") (part "R-US_R0201"))
    )
    (comp (ref "R20")
      (value "50")
      (footprint "eagle-import:R0201")
      (fields (field (name "MANUFACTURER") "Panasonic Electronic Components"))
      (libsource (lib "eagle-import") (part "R-US_R0201"))
    )
    (comp (ref "R23")
      (value "50")
      (footprint "eagle-import:R0201")
      (fields (field (name "MANUFACTURER") "Panasonic Electronic Components"))
      (libsource (lib "eagle-import") (part "R-US_R0201"))
    )
    (comp (ref "U5")
      (value "AS3661WL-CSP-25")
      (footprint "eagle-import:WL-CSP-25")
      (fields (field (name "MANUFACTURER") "Texas Instruments"))
      (libsource (lib "eagle-import") (part "AS3661WL-CSP-25"))
    )
  )
  (nets
    (net (code "1") (name "ACC_CSN") (class "Default")
      (node (ref "U1") (pin "36") (pinfunction "PD8/BU_VIN/CMU_CLK1#1_36") (pintype "bidirectional"))
      (node (ref "U3") (pin "8") (pinfunction "CS_8") (pintype "bidirectional"))
    )
    (net (code "2") (name "ACC_INT") (class "Default")
      (node (ref "U1") (pin "5") (pinfunction "PA4/ETM_TD2#3/LES_ALTEX3/TIM0_CDTI1#0_5") (pintype "bidirectional"))
      (node (ref "U1") (pin "6") (pinfunction "PA5/ETM_TD3#3/LES_ALTEX4/LEU1_TX#1/TIM0_CDTI2#0_6") (pintype "bidirectional"))
      (node (ref "U3") (pin "11") (pinfunction "INT1_11") (pintype "bidirectional"))
    )
    (net (code "3") (name "BAT_V") (class "Default")
      (node (ref "B+") (pin "1") (pinfunction "1_1") (pintype "bidirectional"))
      (node (ref "BAT1") (pin "1") (pinfunction "1_1") (pintype "bidirectional"))
      (node (ref "C4") (pin "1") (pinfunction "1_1") (pintype "passive"))
      (node (ref "C51") (pin "1") (pinfunction "1_1") (pintype "passive"))
      (node (ref "R33") (pin "1") (pinfunction "1_1") (pintype "passive"))
      (node (ref "U14") (pin "3") (pinfunction "D_3") (pintype "passive"))
      (node (ref "U6") (pin "4") (pinfunction "S2_4") (pintype "passive"))
      (node (ref "U7") (pin "3") (pinfunction "VBAT_3") (pintype "bidirectional"))
      (node (ref "U7") (pin "4") (pinfunction "VBAT_4") (pintype "bidirectional"))
    )
    (net (code "4") (name "BAT_V{slash}2") (class "Default")
      (node (ref "R31") (pin "2") (pinfunction "2_2") (pintype "passive"))
      (node (ref "R32") (pin "1") (pinfunction "1_1") (pintype "passive"))
      (node (ref "U1") (pin "34") (pinfunction "PD6/ACMP0_O#2/ADC0_CH6/DAC0_P1/OPAMP_P1/ETM_TD0#0/I2C0_SDA#1/LES_ALTEX0/LETIM0_OUT0#0/PCNT0_S0IN#3/TIM1_CC0#4/US1_RX#2_34") (pintype "bidirectional"))
    )
    (net (code "5") (name "BAT_V{slash}2EN") (class "Default")
      (node (ref "U1") (pin "51") (pinfunction "PF2/ACMP1_O#0/DBG_SWO#0/GPIO_EM4WU4/LEU0_TX#4/TIM0_CC2#5_51") (pintype "bidirectional"))
      (node (ref "U6") (pin "2") (pinfunction "G1_2") (pintype "passive"))
    )
    (net (code "6") (name "CHG_RATE") (class "Default")
      (node (ref "R8") (pin "2") (pinfunction "2_2") (pintype "passive"))
      (node (ref "U1") (pin "35") (pinfunction "PD7/ACMP1_O#2/ADC0_CH7/CMU_CLK0#2/DAC0_N1/OPAMP_N1/ETM_TCLK#0/I2C0_SCL#1/LES_ALTEX1/LETIM0_OUT1#0/PCNT0_S1IN#3/TIM1_CC1#4/US1_TX#2_35") (pintype "bidirectional"))
      (node (ref "U7") (pin "8") (pinfunction "PROG_8") (pintype "bidirectional"))
    )
    (net (code "7") (name "CHG_STAT") (class "Default")
      (node (ref "R15") (pin "2") (pinfunction "2_2") (pintype "passive"))
      (node (ref "U1") (pin "42") (pinfunction "PC9/ACMP1_CH1/GPIO_EM4WU2/LES_CH9/TIM2_CC1#2/US0_CLK#2_42") (pintype "bidirectional"))
      (node (ref "U7") (pin "5") (pinfunction "STAT_5") (pintype "bidirectional"))
    )
    (net (code "8") (name "CLK32K") (class "Default")
      (node (ref "U1") (pin "2") (pinfunction "PA1/CMU_CLK1#0/I2C0_SCL#0/PRS_CH1/TIM0_CC1#0,1_2") (pintype "bidirectional"))
      (node (ref "U2") (pin "5") (pinfunction "XL1_5") (pintype "bidirectional"))
    )
    (net (code "9") (name "GND") (class "Default")
      (node (ref "B-") (pin "1") (pinfunction "1_1") (pintype "bidirectional"))
      (node (ref "C1") (pin "2") (pinfunction "2_2") (pintype "passive"))
      (node (ref "C10") (pin "2") (pinfunction "2_2") (pintype "passive"))
      (node (ref "C11") (pin "2") (pinfunction "2_2") (pintype "passive"))
      (node (ref "C12") (pin "2") (pinfunction "2_2") (pintype "passive"))
      (node (ref "C13") (pin "2") (pinfunction "2_2") (pintype "passive"))
      (node (ref "C14") (pin "2") (pinfunction "2_2") (pintype "passive"))
      (node (ref "C15") (pin "2") (pinfunction "2_2") (pintype "passive"))
      (node (ref "C16") (pin "2") (pinfunction "2_2") (pintype "passive"))
      (node (ref "C17") (pin "2") (pinfunction "2_2") (pintype "passive"))
      (node (ref "C18") (pin "2") (pinfunction "2_2") (pintype "passive"))
      (node (ref "C19") (pin "2") (pinfunction "2_2") (pintype "passive"))
      (node (ref "C2") (pin "2") (pinfunction "2_2") (pintype "passive"))
      (node (ref "C20") (pin "2") (pinfunction "2_2") (pintype "passive"))
      (node (ref "C21") (pin "2") (pinfunction "2_2") (pintype "passive"))
      (node (ref "C22") (pin "2") (pinfunction "2_2") (pintype "passive"))
      (node (ref "C23") (pin "2") (pinfunction "2_2") (pintype "passive"))
      (node (ref "C24") (pin "2") (pinfunction "2_2") (pintype "passive"))
      (node (ref "C25") (pin "2") (pinfunction "2_2") (pintype "passive"))
      (node (ref "C26") (pin "2") (pinfunction "2_2") (pintype "passive"))
      (node (ref "C27") (pin "2") (pinfunction "2_2") (pintype "passive"))
      (node (ref "C28") (pin "2") (pinfunction "2_2") (pintype "passive"))
      (node (ref "C29") (pin "2") (pinfunction "2_2") (pintype "passive"))
      (node (ref "C3") (pin "2") (pinfunction "2_2") (pintype "passive"))
      (node (ref "C30") (pin "2") (pinfunction "2_2") (pintype "passive"))
      (node (ref "C31") (pin "2") (pinfunction "2_2") (pintype "passive"))
      (node (ref "C32") (pin "2") (pinfunction "2_2") (pintype "passive"))
      (node (ref "C33") (pin "2") (pinfunction "2_2") (pintype "passive"))
      (node (ref "C34") (pin "2") (pinfunction "2_2") (pintype "passive"))
      (node (ref "C35") (pin "2") (pinfunction "2_2") (pintype "passive"))
      (node (ref "C36") (pin "2") (pinfunction "2_2") (pintype "passive"))
      (node (ref "C39") (pin "2") (pinfunction "2_2") (pintype "passive"))
      (node (ref "C4") (pin "2") (pinfunction "2_2") (pintype "passive"))
      (node (ref "C40") (pin "2") (pinfunction "2_2") (pintype "passive"))
      (node (ref "C41") (pin "2") (pinfunction "2_2") (pintype "passive"))
      (node (ref "C42") (pin "2") (pinfunction "2_2") (pintype "passive"))
      (node (ref "C43") (pin "2") (pinfunction "2_2") (pintype "passive"))
      (node (ref "C44") (pin "2") (pinfunction "2_2") (pintype "passive"))
      (node (ref "C45") (pin "2") (pinfunction "2_2") (pintype "passive"))
      (node (ref "C46") (pin "2") (pinfunction "2_2") (pintype "passive"))
      (node (ref "C48") (pin "2") (pinfunction "2_2") (pintype "passive"))
      (node (ref "C5") (pin "2") (pinfunction "2_2") (pintype "passive"))
      (node (ref "C50") (pin "2") (pinfunction "2_2") (pintype "passive"))
      (node (ref "C51") (pin "2") (pinfunction "2_2") (pintype "passive"))
      (node (ref "C52") (pin "2") (pinfunction "2_2") (pintype "passive"))
      (node (ref "C55") (pin "2") (pinfunction "2_2") (pintype "passive"))
      (node (ref "C6") (pin "2") (pinfunction "2_2") (pintype "passive"))
      (node (ref "C7") (pin "2") (pinfunction "2_2") (pintype "passive"))
      (node (ref "C8") (pin "2") (pinfunction "2_2") (pintype "passive"))
      (node (ref "C9") (pin "2") (pinfunction "2_2") (pintype "passive"))
      (node (ref "D1") (pin "1") (pinfunction "BC_1") (pintype "passive"))
      (node (ref "D1") (pin "3") (pinfunction "RC_3") (pintype "passive"))
      (node (ref "D1") (pin "5") (pinfunction "GC_5") (pintype "passive"))
      (node (ref "D2") (pin "1") (pinfunction "BC_1") (pintype "passive"))
      (node (ref "D2") (pin "3") (pinfunction "RC_3") (pintype "passive"))
      (node (ref "D2") (pin "5") (pinfunction "GC_5") (pintype "passive"))
      (node (ref "D3") (pin "1") (pinfunction "BC_1") (pintype "passive"))
      (node (ref "D3") (pin "3") (pinfunction "RC_3") (pintype "passive"))
      (node (ref "D3") (pin "5") (pinfunction "GC_5") (pintype "passive"))
      (node (ref "J2") (pin "3") (pinfunction "3_3") (pintype "bidirectional"))
      (node (ref "JPDEBUG") (pin "5") (pinfunction "GND_5") (pintype "bidirectional"))
      (node (ref "L4") (pin "1") (pinfunction "1_1") (pintype "passive"))
      (node (ref "R10") (pin "2") (pinfunction "2_2") (pintype "passive"))
      (node (ref "R11") (pin "1") (pinfunction "1_1") (pintype "passive"))
      (node (ref "R12") (pin "2") (pinfunction "2_2") (pintype "passive"))
      (node (ref "R32") (pin "2") (pinfunction "2_2") (pintype "passive"))
      (node (ref "R4") (pin "2") (pinfunction "2_2") (pintype "passive"))
      (node (ref "R8") (pin "1") (pinfunction "1_1") (pintype "passive"))
      (node (ref "U1") (pin "65") (pinfunction "VSS_65") (pintype "passive"))
      (node (ref "U10") (pin "2") (pinfunction "GND_2") (pintype "bidirectional"))
      (node (ref "U10") (pin "5") (pinfunction "GND_5") (pintype "bidirectional"))
      (node (ref "U10") (pin "6") (pinfunction "GND_6") (pintype "bidirectional"))
      (node (ref "U11") (pin "3") (pinfunction "GND1_3") (pintype "bidirectional"))
      (node (ref "U11") (pin "5") (pinfunction "GND2_5") (pintype "bidirectional"))
      (node (ref "U11") (pin "TP") (pinfunction "GND3_TP") (pintype "bidirectional"))
      (node (ref "U12") (pin "2") (pinfunction "GND1_2") (pintype "bidirectional"))
      (node (ref "U12") (pin "TP") (pinfunction "GND2_TP") (pintype "bidirectional"))
      (node (ref "U13") (pin "4") (pinfunction "GND1_4") (pintype "bidirectional"))
      (node (ref "U13") (pin "5") (pinfunction "GND2_5") (pintype "bidirectional"))
      (node (ref "U13") (pin "6") (pinfunction "~{E}_6") (pintype "bidirectional"))
      (node (ref "U16") (pin "D2") (pinfunction "GND_D2") (pintype "bidirectional"))
      (node (ref "U17") (pin "B2") (pinfunction "GND_B2") (pintype "bidirectional"))
      (node (ref "U18") (pin "6") (pinfunction "GND_6") (pintype "bidirectional"))
      (node (ref "U2") (pin "17") (pinfunction "VSS_17_17") (pintype "bidirectional"))
      (node (ref "U2") (pin "18") (pinfunction "VSS_18_18") (pintype "bidirectional"))
      (node (ref "U2") (pin "23") (pinfunction "VSS_23_23") (pintype "bidirectional"))
      (node (ref "U2") (pin "30") (pinfunction "VSS_30_30") (pintype "bidirectional"))
      (node (ref "U2") (pin "31") (pinfunction "VSS_31_31") (pintype "bidirectional"))
      (node (ref "U2") (pin "33") (pinfunction "GND_33") (pintype "bidirectional"))
      (node (ref "U2") (pin "8") (pinfunction "VSS_8_8") (pintype "bidirectional"))
      (node (ref "U3") (pin "10") (pinfunction "RES_10") (pintype "bidirectional"))
      (node (ref "U3") (pin "12") (pinfunction "GND12_12") (pintype "bidirectional"))
      (node (ref "U3") (pin "5") (pinfunction "GND5_5") (pintype "bidirectional"))
      (node (ref "U4") (pin "10") (pinfunction "GND_10_10") (pintype "bidirectional"))
      (node (ref "U4") (pin "5") (pinfunction "GND_5_5") (pintype "bidirectional"))
      (node (ref "U5") (pin "B3") (pinfunction "ASEL1_B3") (pintype "bidirectional"))
      (node (ref "U5") (pin "C3") (pinfunction "ASEL0_C3") (pintype "bidirectional"))
      (node (ref "U5") (pin "D4") (pinfunction "CLK32K_D4") (pintype "bidirectional"))
      (node (ref "U5") (pin "D5") (pinfunction "GND_D5") (pintype "bidirectional"))
      (node (ref "U5") (pin "E3") (pinfunction "TRIG_E3") (pintype "bidirectional"))
      (node (ref "U6") (pin "1") (pinfunction "S1_1") (pintype "passive"))
      (node (ref "U7") (pin "6") (pinfunction "VSS_6") (pintype "bidirectional"))
      (node (ref "U7") (pin "PGND") (pinfunction "VSS_PGND") (pintype "bidirectional"))
      (node (ref "U8") (pin "B1") (pinfunction "GND_B1") (pintype "passive"))
      (node (ref "U9") (pin "6") (pinfunction "GND6_6") (pintype "bidirectional"))
      (node (ref "U9") (pin "7") (pinfunction "GND7_7") (pintype "bidirectional"))
      (node (ref "X2") (pin "2") (pinfunction "GND1_2") (pintype "bidirectional"))
      (node (ref "X2") (pin "4") (pinfunction "GND2_4") (pintype "bidirectional"))
      (node (ref "X4") (pin "2") (pinfunction "GND1_2") (pintype "bidirectional"))
      (node (ref "X4") (pin "4") (pinfunction "GND2_4") (pintype "bidirectional"))
    )
    (net (code "10") (name "I2C0_INT") (class "Default")
      (node (ref "J2") (pin "6") (pinfunction "6_6") (pintype "bidirectional"))
      (node (ref "U1") (pin "41") (pinfunction "PC8/ACMP1_CH0/LES_CH8/TIM2_CC0#2/US0_CS#2_41") (pintype "bidirectional"))
    )
    (net (code "11") (name "I2C0_SCL") (class "Default")
      (node (ref "J2") (pin "4") (pinfunction "4_4") (pintype "bidirectional"))
      (node (ref "U1") (pin "38") (pinfunction "PC7/ACMP0_CH7/ETM_TD0#2/I2C0_SCL#2/LES_CH7/LEU1_RX#0_38") (pintype "bidirectional"))
    )
    (net (code "12") (name "I2C0_SDA") (class "Default")
      (node (ref "J2") (pin "1") (pinfunction "1_1") (pintype "bidirectional"))
      (node (ref "U1") (pin "37") (pinfunction "PC6/ACMP0_CH6/ETM_TCLK#2/I2C0_SDA#2/LES_CH6/LEU1_TX#0_37") (pintype "bidirectional"))
    )
    (net (code "13") (name "I2C1_PWR") (class "Default")
      (node (ref "U1") (pin "18") (pinfunction "PA9/TIM2_CC1#0_18") (pintype "bidirectional"))
      (node (ref "U9") (pin "1") (pinfunction "ON_1") (pintype "bidirectional"))
    )
    (net (code "14") (name "I2C1_SCL") (class "Default")
      (node (ref "R1") (pin "1") (pinfunction "1_1") (pintype "passive"))
      (node (ref "U1") (pin "22") (pinfunction "PB12/DAC0_OUT1/OPAMP_OUT1/I2C1_SCL#1/LETIM0_OUT1#1_22") (pintype "bidirectional"))
      (node (ref "U4") (pin "7") (pinfunction "SCL_7") (pintype "bidirectional"))
      (node (ref "U5") (pin "E5") (pinfunction "SCL_E5") (pintype "bidirectional"))
    )
    (net (code "15") (name "I2C1_SDA") (class "Default")
      (node (ref "R9") (pin "1") (pinfunction "1_1") (pintype "passive"))
      (node (ref "U1") (pin "21") (pinfunction "PB11/DAC0_OUT0/OPAMP_OUT0/I2C1_SDA#1/LETIM0_OUT0#1/TIM1_CC2#3_21") (pintype "bidirectional"))
      (node (ref "U4") (pin "6") (pinfunction "SDA_6") (pintype "bidirectional"))
      (node (ref "U5") (pin "E4") (pinfunction "SDA_E4") (pintype "bidirectional"))
    )
    (net (code "16") (name "I2C1_V+") (class "Default")
      (node (ref "C12") (pin "1") (pinfunction "1_1") (pintype "passive"))
      (node (ref "C13") (pin "1") (pinfunction "1_1") (pintype "passive"))
      (node (ref "C14") (pin "1") (pinfunction "1_1") (pintype "passive"))
      (node (ref "C2") (pin "1") (pinfunction "1_1") (pintype "passive"))
      (node (ref "R1") (pin "2") (pinfunction "2_2") (pintype "passive"))
      (node (ref "R5") (pin "1") (pinfunction "1_1") (pintype "passive"))
      (node (ref "R9") (pin "2") (pinfunction "2_2") (pintype "passive"))
      (node (ref "U4") (pin "2") (pinfunction "VDD_2") (pintype "bidirectional"))
      (node (ref "U4") (pin "8") (pinfunction "VDDIO_8") (pintype "bidirectional"))
      (node (ref "U9") (pin "4") (pinfunction "VOUT4_4") (pintype "bidirectional"))
      (node (ref "U9") (pin "5") (pinfunction "VOUT5_5") (pintype "bidirectional"))
    )
    (net (code "17") (name "LED0") (class "Default")
      (node (ref "R20") (pin "1") (pinfunction "1_1") (pintype "passive"))
      (node (ref "U1") (pin "10") (pinfunction "PC1/ACMP0_CH1/DAC0_OUT0ALT/OPAMP_OUT0ALT#1/I2C0_SCL#4/LES_CH1/PCNT0_S1IN#2/PRS_CH3#0/TIM0_CC2#4/US0_RX#5/US1_RX#0_10") (pintype "bidirectional"))
    )
    (net (code "18") (name "LED4") (class "Default")
      (node (ref "R23") (pin "1") (pinfunction "1_1") (pintype "passive"))
      (node (ref "U1") (pin "9") (pinfunction "PC0/ACMP0_CH0/DAC0_OUT0ALT/OPAMP_OUT0ALT#0/I2C0_SDA#4/LES_CH0/PCNT0_S0IN#2/PRS_CH2#0/TIM0_CC1#4/US0_TX#5/US1_TX#0_9") (pintype "bidirectional"))
    )
    (net (code "19") (name "LED5") (class "Default")
      (node (ref "R17") (pin "1") (pinfunction "1_1") (pintype "passive"))
      (node (ref "U1") (pin "57") (pinfunction "PE9/PCNT2_S1IN#1_57") (pintype "bidirectional"))
    )
    (net (code "20") (name "LED6") (class "Default")
      (node (ref "R6") (pin "1") (pinfunction "1_1") (pintype "passive"))
      (node (ref "U1") (pin "64") (pinfunction "PA15/TIM3_CC2_64") (pintype "bidirectional"))
    )
    (net (code "21") (name "LED_EN") (class "Default")
      (node (ref "U1") (pin "17") (pinfunction "PA8/TIM2_CC0#0_17") (pintype "bidirectional"))
      (node (ref "U5") (pin "C4") (pinfunction "EN_C4") (pintype "bidirectional"))
    )
    (net (code "22") (name "MAG_INT") (class "Default")
      (node (ref "U1") (pin "19") (pinfunction "PA10/TIM2_CC2#0_19") (pintype "bidirectional"))
      (node (ref "U4") (pin "9") (pinfunction "INT1_9") (pintype "bidirectional"))
    )
    (net (code "23") (name "MEM_CSN") (class "Default")
      (node (ref "U1") (pin "3") (pinfunction "PA2/CMU_CLK0#0/ETM_TD0#3/TIM0_CC2#0,1_3") (pintype "bidirectional"))
      (node (ref "U18") (pin "8") (pinfunction "B3_8") (pintype "bidirectional"))
    )
    (net (code "24") (name "NRESET") (class "Default")
      (node (ref "JPDEBUG") (pin "3") (pinfunction "NRESET_3") (pintype "bidirectional"))
      (node (ref "U1") (pin "20") (pinfunction "RESETN_20") (pintype "passive"))
      (node (ref "U10") (pin "1") (pinfunction "~{RST}_1") (pintype "bidirectional"))
    )
    (net (code "25") (name "NRF_RDYN") (class "Default")
      (node (ref "U1") (pin "32") (pinfunction "PD4/ADC0_CH4/DAC0_P2/OPAMP_P2/ETM_TD2#0,2/LEU0_TX#0_32") (pintype "bidirectional"))
      (node (ref "U2") (pin "16") (pinfunction "RDYN_16") (pintype "bidirectional"))
    )
    (net (code "26") (name "NRF_REQN") (class "Default")
      (node (ref "U1") (pin "31") (pinfunction "PD3/ADC0_CH3/DAC0_N2/OPAMP_N2/ETM_TD1#0,2/TIM0_CC2#3/US1_CS#1_31") (pintype "bidirectional"))
      (node (ref "U2") (pin "12") (pinfunction "REQN_12") (pintype "bidirectional"))
    )
    (net (code "27") (name "NRF_RESETN") (class "Default")
      (node (ref "U1") (pin "33") (pinfunction "PD5/ADC0_CH5/DAC0_OUT2/OPAMP_OUT2#0/ETM_TD3#0,2/LEU0_RX#0_33") (pintype "bidirectional"))
      (node (ref "U2") (pin "19") (pinfunction "RESETN_19") (pintype "bidirectional"))
    )
    (net (code "28") (name "Net-(A1-A)") (class "Default")
      (node (ref "A1") (pin "FP") (pinfunction "A_FP") (pintype "bidirectional"))
      (node (ref "C7") (pin "1") (pinfunction "1_1") (pintype "passive"))
      (node (ref "L6") (pin "2") (pinfunction "2_2") (pintype "passive"))
    )
    (net (code "29") (name "Net-(C46-Pad1)") (class "Default")
      (node (ref "C46") (pin "1") (pinfunction "1_1") (pintype "passive"))
      (node (ref "C47") (pin "2") (pinfunction "2_2") (pintype "passive"))
      (node (ref "C6") (pin "1") (pinfunction "1_1") (pintype "passive"))
      (node (ref "L6") (pin "1") (pinfunction "1_1") (pintype "passive"))
    )
    (net (code "30") (name "Net-(C47-Pad1)") (class "Default")
      (node (ref "C47") (pin "1") (pinfunction "1_1") (pintype "passive"))
      (node (ref "L3") (pin "2") (pinfunction "2_2") (pintype "passive"))
    )
    (net (code "31") (name "Net-(D0-PadC)") (class "Default")
      (node (ref "D0") (pin "C") (pinfunction "C_C") (pintype "passive"))
      (node (ref "R20") (pin "2") (pinfunction "2_2") (pintype "passive"))
    )
    (net (code "32") (name "Net-(D1-BA)") (class "Default")
      (node (ref "D1") (pin "2") (pinfunction "BA_2") (pintype "passive"))
      (node (ref "U5") (pin "C2") (pinfunction "LED6_C2") (pintype "bidirectional"))
    )
    (net (code "33") (name "Net-(D1-GA)") (class "Default")
      (node (ref "D1") (pin "6") (pinfunction "GA_6") (pintype "passive"))
      (node (ref "U5") (pin "C1") (pinfunction "LED5_C1") (pintype "bidirectional"))
    )
    (net (code "34") (name "Net-(D1-RA)") (class "Default")
      (node (ref "D1") (pin "4") (pinfunction "RA_4") (pintype "passive"))
      (node (ref "U5") (pin "E1") (pinfunction "LED9_E1") (pintype "bidirectional"))
    )
    (net (code "35") (name "Net-(D2-BA)") (class "Default")
      (node (ref "D2") (pin "2") (pinfunction "BA_2") (pintype "passive"))
      (node (ref "U5") (pin "B2") (pinfunction "LED4_B2") (pintype "bidirectional"))
    )
    (net (code "36") (name "Net-(D2-GA)") (class "Default")
      (node (ref "D2") (pin "6") (pinfunction "GA_6") (pintype "passive"))
      (node (ref "U5") (pin "B1") (pinfunction "LED3_B1") (pintype "bidirectional"))
    )
    (net (code "37") (name "Net-(D2-RA)") (class "Default")
      (node (ref "D2") (pin "4") (pinfunction "RA_4") (pintype "passive"))
      (node (ref "U5") (pin "D2") (pinfunction "LED8_D2") (pintype "bidirectional"))
    )
    (net (code "38") (name "Net-(D3-BA)") (class "Default")
      (node (ref "D3") (pin "2") (pinfunction "BA_2") (pintype "passive"))
      (node (ref "U5") (pin "A2") (pinfunction "LED2_A2") (pintype "bidirectional"))
    )
    (net (code "39") (name "Net-(D3-GA)") (class "Default")
      (node (ref "D3") (pin "6") (pinfunction "GA_6") (pintype "passive"))
      (node (ref "U5") (pin "A1") (pinfunction "LED1_A1") (pintype "bidirectional"))
    )
    (net (code "40") (name "Net-(D3-RA)") (class "Default")
      (node (ref "D3") (pin "4") (pinfunction "RA_4") (pintype "passive"))
      (node (ref "U5") (pin "D1") (pinfunction "LED7_D1") (pintype "bidirectional"))
    )
    (net (code "41") (name "Net-(D4-PadC)") (class "Default")
      (node (ref "D4") (pin "C") (pinfunction "C_C") (pintype "passive"))
      (node (ref "R23") (pin "2") (pinfunction "2_2") (pintype "passive"))
    )
    (net (code "42") (name "Net-(D5-PadC)") (class "Default")
      (node (ref "D5") (pin "C") (pinfunction "C_C") (pintype "passive"))
      (node (ref "R17") (pin "2") (pinfunction "2_2") (pintype "passive"))
    )
    (net (code "43") (name "Net-(D6-PadC)") (class "Default")
      (node (ref "D6") (pin "C") (pinfunction "C_C") (pintype "passive"))
      (node (ref "R6") (pin "2") (pinfunction "2_2") (pintype "passive"))
    )
    (net (code "44") (name "Net-(D10-PadA)") (class "Default")
      (node (ref "D10") (pin "A") (pinfunction "A_A") (pintype "passive"))
      (node (ref "L9") (pin "2") (pinfunction "2_2") (pintype "passive"))
    )
    (net (code "45") (name "Net-(J1-5V)") (class "Default")
      (node (ref "J1") (pin "1") (pinfunction "5V_1") (pintype "bidirectional"))
      (node (ref "L9") (pin "1") (pinfunction "1_1") (pintype "passive"))
      (node (ref "U8") (pin "A2") (pinfunction "VBUS_A2") (pintype "passive"))
      (node (ref "USBV") (pin "1") (pinfunction "1_1") (pintype "bidirectional"))
    )
    (net (code "46") (name "Net-(J1-D+)") (class "Default")
      (node (ref "J1") (pin "3") (pinfunction "D+_3") (pintype "bidirectional"))
      (node (ref "R28") (pin "1") (pinfunction "1_1") (pintype "passive"))
      (node (ref "U8") (pin "C1") (pinfunction "IO3_C1") (pintype "passive"))
      (node (ref "USBD+") (pin "1") (pinfunction "1_1") (pintype "bidirectional"))
    )
    (net (code "47") (name "Net-(J1-D-)") (class "Default")
      (node (ref "J1") (pin "2") (pinfunction "D-_2") (pintype "bidirectional"))
      (node (ref "R27") (pin "1") (pinfunction "1_1") (pintype "passive"))
      (node (ref "U8") (pin "A1") (pinfunction "IO2_A1") (pintype "passive"))
      (node (ref "USBD-") (pin "1") (pinfunction "1_1") (pintype "bidirectional"))
    )
    (net (code "48") (name "Net-(J1-GND)") (class "Default")
      (node (ref "J1") (pin "5") (pinfunction "GND_5") (pintype "bidirectional"))
      (node (ref "L4") (pin "2") (pinfunction "2_2") (pintype "passive"))
    )
    (net (code "49") (name "Net-(J1-ID)") (class "Default")
      (node (ref "J1") (pin "4") (pinfunction "ID_4") (pintype "bidirectional"))
      (node (ref "R13") (pin "1") (pinfunction "1_1") (pintype "passive"))
      (node (ref "U8") (pin "C2") (pinfunction "IO1_C2") (pintype "passive"))
    )
    (net (code "50") (name "Net-(U1B-PB7{slash}LFXTAL_P{slash}TIM1_CC0#3{slash}US0_TX#4{slash}US1_CLK#0)") (class "Default")
      (node (ref "C33") (pin "1") (pinfunction "1_1") (pintype "passive"))
      (node (ref "U1") (pin "15") (pinfunction "PB7/LFXTAL_P/TIM1_CC0#3/US0_TX#4/US1_CLK#0_15") (pintype "bidirectional"))
      (node (ref "X1") (pin "1") (pinfunction "1_1") (pintype "passive"))
    )
    (net (code "51") (name "Net-(U1B-PB8{slash}LFXTAL_N{slash}TIM1_CC1#3{slash}US0_RX#4{slash}US1_CS#0)") (class "Default")
      (node (ref "C32") (pin "1") (pinfunction "1_1") (pintype "passive"))
      (node (ref "U1") (pin "16") (pinfunction "PB8/LFXTAL_N/TIM1_CC1#3/US0_RX#4/US1_CS#0_16") (pintype "bidirectional"))
      (node (ref "X1") (pin "2") (pinfunction "2_2") (pintype "passive"))
    )
    (net (code "52") (name "Net-(U1B-PB13{slash}HFXTAL_P{slash}LEU0_TX#1{slash}US0_CLK#4,5)") (class "Default")
      (node (ref "C22") (pin "1") (pinfunction "1_1") (pintype "passive"))
      (node (ref "U1") (pin "24") (pinfunction "PB13/HFXTAL_P/LEU0_TX#1/US0_CLK#4,5_24") (pintype "bidirectional"))
      (node (ref "X4") (pin "1") (pinfunction "1_1") (pintype "passive"))
    )
    (net (code "53") (name "Net-(U1B-PB14{slash}HFXTAL_N{slash}LEU0_RX#1{slash}US0_CS#4,5)") (class "Default")
      (node (ref "C48") (pin "1") (pinfunction "1_1") (pintype "passive"))
      (node (ref "U1") (pin "25") (pinfunction "PB14/HFXTAL_N/LEU0_RX#1/US0_CS#4,5_25") (pintype "bidirectional"))
      (node (ref "X4") (pin "3") (pinfunction "2_3") (pintype "passive"))
    )
    (net (code "54") (name "Net-(U1G-AVDD_0)") (class "Default")
      (node (ref "C25") (pin "1") (pinfunction "1_1") (pintype "passive"))
      (node (ref "C26") (pin "1") (pinfunction "1_1") (pintype "passive"))
      (node (ref "C27") (pin "1") (pinfunction "1_1") (pintype "passive"))
      (node (ref "C28") (pin "1") (pinfunction "1_1") (pintype "passive"))
      (node (ref "C29") (pin "1") (pinfunction "1_1") (pintype "passive"))
      (node (ref "C30") (pin "1") (pinfunction "1_1") (pintype "passive"))
      (node (ref "C31") (pin "1") (pinfunction "1_1") (pintype "passive"))
      (node (ref "R25") (pin "1") (pinfunction "1_1") (pintype "passive"))
      (node (ref "U1") (pin "23") (pinfunction "AVDD_1_23") (pintype "passive"))
      (node (ref "U1") (pin "26") (pinfunction "IOVDD_3_26") (pintype "passive"))
      (node (ref "U1") (pin "27") (pinfunction "AVDD_0_27") (pintype "passive"))
      (node (ref "U1") (pin "39") (pinfunction "VDD_DREG_39") (pintype "passive"))
      (node (ref "U1") (pin "55") (pinfunction "IOVDD_5_55") (pintype "passive"))
      (node (ref "U1") (pin "8") (pinfunction "IOVDD_0_8") (pintype "passive"))
    )
    (net (code "55") (name "Net-(U1G-DECOUPLE)") (class "Default")
      (node (ref "C24") (pin "1") (pinfunction "1_1") (pintype "passive"))
      (node (ref "U1") (pin "40") (pinfunction "DECOUPLE_40") (pintype "passive"))
    )
    (net (code "56") (name "Net-(U1G-USB_VREGO)") (class "Default")
      (node (ref "C8") (pin "1") (pinfunction "1_1") (pintype "passive"))
      (node (ref "U1") (pin "46") (pinfunction "USB_VREGO_46") (pintype "passive"))
    )
    (net (code "57") (name "Net-(U2-ANT1)") (class "Default")
      (node (ref "L1") (pin "1") (pinfunction "1_1") (pintype "passive"))
      (node (ref "L2") (pin "2") (pinfunction "2_2") (pintype "passive"))
      (node (ref "U2") (pin "21") (pinfunction "ANT1_21") (pintype "bidirectional"))
    )
    (net (code "58") (name "Net-(U2-ANT2)") (class "Default")
      (node (ref "L1") (pin "2") (pinfunction "2_2") (pintype "passive"))
      (node (ref "L3") (pin "1") (pinfunction "1_1") (pintype "passive"))
      (node (ref "U2") (pin "22") (pinfunction "ANT2_22") (pintype "bidirectional"))
    )
    (net (code "59") (name "Net-(U2-DEC1)") (class "Default")
      (node (ref "C41") (pin "1") (pinfunction "1_1") (pintype "passive"))
      (node (ref "U2") (pin "2") (pinfunction "DEC1_2") (pintype "bidirectional"))
    )
    (net (code "60") (name "Net-(U2-DEC2)") (class "Default")
      (node (ref "C40") (pin "1") (pinfunction "1_1") (pintype "passive"))
      (node (ref "U2") (pin "3") (pinfunction "DEC2_3") (pintype "bidirectional"))
    )
    (net (code "61") (name "Net-(U2-IREF)") (class "Default")
      (node (ref "R11") (pin "2") (pinfunction "2_2") (pintype "passive"))
      (node (ref "U2") (pin "25") (pinfunction "IREF_25") (pintype "bidirectional"))
    )
    (net (code "62") (name "Net-(U2-VDD_PA)") (class "Default")
      (node (ref "C44") (pin "1") (pinfunction "1_1") (pintype "passive"))
      (node (ref "C45") (pin "1") (pinfunction "1_1") (pintype "passive"))
      (node (ref "L2") (pin "1") (pinfunction "1_1") (pintype "passive"))
      (node (ref "U2") (pin "20") (pinfunction "VDD_PA_20") (pintype "bidirectional"))
    )
    (net (code "63") (name "Net-(U2-XC1)") (class "Default")
      (node (ref "C35") (pin "1") (pinfunction "1_1") (pintype "passive"))
      (node (ref "U2") (pin "28") (pinfunction "XC1_28") (pintype "bidirectional"))
      (node (ref "X2") (pin "1") (pinfunction "1_1") (pintype "passive"))
    )
    (net (code "64") (name "Net-(U2-XC2)") (class "Default")
      (node (ref "C34") (pin "1") (pinfunction "1_1") (pintype "passive"))
      (node (ref "U2") (pin "27") (pinfunction "XC2_27") (pintype "bidirectional"))
      (node (ref "X2") (pin "3") (pinfunction "2_3") (pintype "passive"))
    )
    (net (code "65") (name "Net-(U4-CAP-A)") (class "Default")
      (node (ref "C16") (pin "1") (pinfunction "1_1") (pintype "passive"))
      (node (ref "U4") (pin "1") (pinfunction "CAP-A_1") (pintype "bidirectional"))
    )
    (net (code "66") (name "Net-(U4-CAP-R)") (class "Default")
      (node (ref "C17") (pin "1") (pinfunction "1_1") (pintype "passive"))
      (node (ref "U4") (pin "4") (pinfunction "CAP-R_4") (pintype "bidirectional"))
    )
    (net (code "67") (name "Net-(U5-C1+)") (class "Default")
      (node (ref "C53") (pin "1") (pinfunction "1_1") (pintype "passive"))
      (node (ref "U5") (pin "B5") (pinfunction "C1+_B5") (pintype "bidirectional"))
    )
    (net (code "68") (name "Net-(U5-C1-)") (class "Default")
      (node (ref "C53") (pin "2") (pinfunction "2_2") (pintype "passive"))
      (node (ref "U5") (pin "B4") (pinfunction "C1-_B4") (pintype "bidirectional"))
    )
    (net (code "69") (name "Net-(U5-C2+)") (class "Default")
      (node (ref "C54") (pin "1") (pinfunction "1_1") (pintype "passive"))
      (node (ref "U5") (pin "A5") (pinfunction "C2+_A5") (pintype "bidirectional"))
    )
    (net (code "70") (name "Net-(U5-C2-)") (class "Default")
      (node (ref "C54") (pin "2") (pinfunction "2_2") (pintype "passive"))
      (node (ref "U5") (pin "A4") (pinfunction "C2-_A4") (pintype "bidirectional"))
    )
    (net (code "71") (name "Net-(U5-VCP)") (class "Default")
      (node (ref "C52") (pin "1") (pinfunction "1_1") (pintype "passive"))
      (node (ref "U5") (pin "A3") (pinfunction "VCP_A3") (pintype "bidirectional"))
    )
    (net (code "72") (name "Net-(U6-D1)") (class "Default")
      (node (ref "R33") (pin "2") (pinfunction "2_2") (pintype "passive"))
      (node (ref "U6") (pin "5") (pinfunction "G2_5") (pintype "passive"))
      (node (ref "U6") (pin "6") (pinfunction "D1_6") (pintype "passive"))
    )
    (net (code "73") (name "Net-(U6-D2)") (class "Default")
      (node (ref "R31") (pin "1") (pinfunction "1_1") (pintype "passive"))
      (node (ref "U6") (pin "3") (pinfunction "D2_3") (pintype "passive"))
    )
    (net (code "74") (name "Net-(U10-~{SR})") (class "Default")
      (node (ref "EXTRESET") (pin "1") (pinfunction "1_1") (pintype "bidirectional"))
      (node (ref "R13") (pin "2") (pinfunction "2_2") (pintype "passive"))
      (node (ref "R2") (pin "2") (pinfunction "2_2") (pintype "passive"))
      (node (ref "U10") (pin "3") (pinfunction "~{SR}_3") (pintype "bidirectional"))
    )
    (net (code "75") (name "Net-(U11-OUT)") (class "Default")
      (node (ref "C21") (pin "1") (pinfunction "1_1") (pintype "passive"))
      (node (ref "R14") (pin "2") (pinfunction "2_2") (pintype "passive"))
      (node (ref "U11") (pin "1") (pinfunction "OUT_1") (pintype "bidirectional"))
      (node (ref "U13") (pin "1") (pinfunction "Y0_1") (pintype "bidirectional"))
      (node (ref "U13") (pin "8") (pinfunction "VCC_8") (pintype "bidirectional"))
    )
    (net (code "76") (name "Net-(U12-FB)") (class "Default")
      (node (ref "R10") (pin "1") (pinfunction "1_1") (pintype "passive"))
      (node (ref "R3") (pin "2") (pinfunction "2_2") (pintype "passive"))
      (node (ref "U12") (pin "4") (pinfunction "FB_4") (pintype "bidirectional"))
    )
    (net (code "77") (name "Net-(U12-SW)") (class "Default")
      (node (ref "L7") (pin "1") (pinfunction "1_1") (pintype "passive"))
      (node (ref "U12") (pin "7") (pinfunction "SW_7") (pintype "bidirectional"))
    )
    (net (code "78") (name "Net-(U12-VOS)") (class "Default")
      (node (ref "C19") (pin "1") (pinfunction "1_1") (pintype "passive"))
      (node (ref "L7") (pin "2") (pinfunction "2_2") (pintype "passive"))
      (node (ref "R3") (pin "1") (pinfunction "1_1") (pintype "passive"))
      (node (ref "U12") (pin "5") (pinfunction "VOS_5") (pintype "bidirectional"))
      (node (ref "U13") (pin "2") (pinfunction "Y1_2") (pintype "bidirectional"))
    )
    (net (code "79") (name "PWR_HIGH") (class "Default")
      (node (ref "U1") (pin "54") (pinfunction "PF5/PRS_CH2#1/TIM0_CDTI2#2,5/USB_VBUSEN_54") (pintype "bidirectional"))
      (node (ref "U12") (pin "1") (pinfunction "EN_1") (pintype "bidirectional"))
    )
    (net (code "80") (name "PWR_MODE") (class "Default")
      (node (ref "U1") (pin "44") (pinfunction "PC11/ACMP1_CH3/LES_CH11/US0_TX#2_44") (pintype "bidirectional"))
      (node (ref "U12") (pin "3") (pinfunction "MODE_3") (pintype "bidirectional"))
    )
    (net (code "81") (name "PWR_SEL") (class "Default")
      (node (ref "R4") (pin "1") (pinfunction "1_1") (pintype "passive"))
      (node (ref "U1") (pin "43") (pinfunction "PC10/ACMP1_CH2/LES_CH10/TIM2_CC2#2/US0_RX#2_43") (pintype "bidirectional"))
      (node (ref "U13") (pin "3") (pinfunction "S_3") (pintype "bidirectional"))
    )
    (net (code "82") (name "SPI0_CLK") (class "Default")
      (node (ref "U16") (pin "C1") (pinfunction "CLK_C1") (pintype "bidirectional"))
      (node (ref "U18") (pin "3") (pinfunction "A2_3") (pintype "bidirectional"))
    )
    (net (code "83") (name "SPI0_CSN") (class "Default")
      (node (ref "R7") (pin "2") (pinfunction "2_2") (pintype "passive"))
      (node (ref "U16") (pin "A2") (pinfunction "~{CS}_A2") (pintype "bidirectional"))
      (node (ref "U18") (pin "4") (pinfunction "A3_4") (pintype "bidirectional"))
    )
    (net (code "84") (name "SPI0_MISO") (class "Default")
      (node (ref "U16") (pin "B2") (pinfunction "DO_B2") (pintype "bidirectional"))
      (node (ref "U18") (pin "5") (pinfunction "A4_5") (pintype "bidirectional"))
    )
    (net (code "85") (name "SPI0_MOSI") (class "Default")
      (node (ref "U16") (pin "D1") (pinfunction "DI_D1") (pintype "bidirectional"))
      (node (ref "U18") (pin "2") (pinfunction "A1_2") (pintype "bidirectional"))
    )
    (net (code "86") (name "SPI0_V+") (class "Default")
      (node (ref "C36") (pin "1") (pinfunction "1_1") (pintype "passive"))
      (node (ref "C55") (pin "1") (pinfunction "1_1") (pintype "passive"))
      (node (ref "R7") (pin "1") (pinfunction "1_1") (pintype "passive"))
      (node (ref "U16") (pin "A1") (pinfunction "VCC_A1") (pintype "bidirectional"))
      (node (ref "U16") (pin "B1") (pinfunction "~{HOLD}_B1") (pintype "bidirectional"))
      (node (ref "U16") (pin "C2") (pinfunction "~{WP}_C2") (pintype "bidirectional"))
      (node (ref "U17") (pin "A2") (pinfunction "OUT_A2") (pintype "bidirectional"))
      (node (ref "U18") (pin "1") (pinfunction "VCCA_1") (pintype "bidirectional"))
      (node (ref "U18") (pin "12") (pinfunction "OE_12") (pintype "bidirectional"))
    )
    (net (code "87") (name "SWCLK") (class "Default")
      (node (ref "JPDEBUG") (pin "4") (pinfunction "SWCLK_4") (pintype "bidirectional"))
      (node (ref "U1") (pin "49") (pinfunction "PF0/DBG_SWCLK#0,1,2,3/I2C0_SDA#5/LETIM0_OUT0#2/LEU0_TX#3/TIM0_CC0#5/US1_CLK#2_49") (pintype "bidirectional"))
    )
    (net (code "88") (name "SWDIO") (class "Default")
      (node (ref "JPDEBUG") (pin "2") (pinfunction "SWDIO_2") (pintype "bidirectional"))
      (node (ref "U1") (pin "50") (pinfunction "PF1/DBG_SWDIO#0,1,2,3/GPIO_EM4WU3/I2C0_SCL#5/LETIM0_OUT1#2/LEU0_RX#3/TIM0_CC1#5/US1_CS#2_50") (pintype "bidirectional"))
    )
    (net (code "89") (name "US0_CLK") (class "Default")
      (node (ref "U1") (pin "60") (pinfunction "PE12/CMU_CLK1#2/I2C0_SDA#6/LES_ALTEX6/TIM1_CC2#1/US0_CLK#0/US0_RX#3_60") (pintype "bidirectional"))
      (node (ref "U18") (pin "9") (pinfunction "B2_9") (pintype "bidirectional"))
    )
    (net (code "90") (name "US0_MISO") (class "Default")
      (node (ref "U1") (pin "59") (pinfunction "PE11/LES_ALTEX5/TIM1_CC1#1/US0_RX#0_59") (pintype "bidirectional"))
      (node (ref "U18") (pin "7") (pinfunction "B4_7") (pintype "bidirectional"))
    )
    (net (code "91") (name "US0_MOSI") (class "Default")
      (node (ref "U1") (pin "58") (pinfunction "PE10/TIM1_CC0#1/US0_TX#0_58") (pintype "bidirectional"))
      (node (ref "U18") (pin "10") (pinfunction "B1_10") (pintype "bidirectional"))
    )
    (net (code "92") (name "US0_PWR") (class "Default")
      (node (ref "U1") (pin "4") (pinfunction "PA3/ETM_TD1#3/LES_ALTEX2/TIM0_CDTI0#0_4") (pintype "bidirectional"))
      (node (ref "U17") (pin "B1") (pinfunction "EN_B1") (pintype "bidirectional"))
    )
    (net (code "93") (name "US1_CLK") (class "Default")
      (node (ref "U1") (pin "30") (pinfunction "PD2/ADC0_CH2/DBG_SWO#3/TIM0_CC1#3/US1_CLK#1/USB_DMPU_30") (pintype "bidirectional"))
      (node (ref "U2") (pin "11") (pinfunction "SCK_11") (pintype "bidirectional"))
      (node (ref "U3") (pin "4") (pinfunction "SPC_4") (pintype "bidirectional"))
    )
    (net (code "94") (name "US1_MISO") (class "Default")
      (node (ref "U1") (pin "29") (pinfunction "PD1/ADC0_CH1/DAC0_OUT1ALT/OPAMP_OUT1ALT#4/DBG_SWO#2/PCNT2_S1IN#0/TIM0_CC0#3/US1_RX#1_29") (pintype "bidirectional"))
      (node (ref "U2") (pin "14") (pinfunction "MISO_14") (pintype "bidirectional"))
      (node (ref "U3") (pin "7") (pinfunction "SDO_7") (pintype "bidirectional"))
    )
    (net (code "95") (name "US1_MOSI") (class "Default")
      (node (ref "U1") (pin "28") (pinfunction "PD0/ADC0_CH0/DAC0_OUT0ALT/OPAMP_OUT0ALT#4/DAC0_OUT2/OPAMP_OUT2#1/PCNT2_S0IN#0/US1_TX#1_28") (pintype "bidirectional"))
      (node (ref "U2") (pin "13") (pinfunction "MOSI_13") (pintype "bidirectional"))
      (node (ref "U3") (pin "6") (pinfunction "SDI_6") (pintype "bidirectional"))
    )
    (net (code "96") (name "USB_DM") (class "Default")
      (node (ref "R27") (pin "2") (pinfunction "2_2") (pintype "passive"))
      (node (ref "U1") (pin "47") (pinfunction "PF10/USB_DM_47") (pintype "bidirectional"))
    )
    (net (code "97") (name "USB_DP") (class "Default")
      (node (ref "R28") (pin "2") (pinfunction "2_2") (pintype "passive"))
      (node (ref "U1") (pin "48") (pinfunction "PF11/USB_DP_48") (pintype "bidirectional"))
    )
    (net (code "98") (name "USB_VBUS") (class "Default")
      (node (ref "C15") (pin "1") (pinfunction "1_1") (pintype "passive"))
      (node (ref "C5") (pin "1") (pinfunction "1_1") (pintype "passive"))
      (node (ref "D10") (pin "C") (pinfunction "C_C") (pintype "passive"))
      (node (ref "R12") (pin "1") (pinfunction "1_1") (pintype "passive"))
      (node (ref "U1") (pin "45") (pinfunction "USB_VREGI_45") (pintype "passive"))
      (node (ref "U1") (pin "52") (pinfunction "USB_VBUS_52") (pintype "passive"))
      (node (ref "U14") (pin "1") (pinfunction "A_1") (pintype "passive"))
      (node (ref "U14") (pin "5") (pinfunction "G_5") (pintype "passive"))
      (node (ref "U7") (pin "1") (pinfunction "VDD_1") (pintype "bidirectional"))
      (node (ref "U7") (pin "2") (pinfunction "VDD_2") (pintype "bidirectional"))
    )
    (net (code "99") (name "VCC") (class "Default")
      (node (ref "C1") (pin "1") (pinfunction "1_1") (pintype "passive"))
      (node (ref "C10") (pin "1") (pinfunction "1_1") (pintype "passive"))
      (node (ref "C11") (pin "1") (pinfunction "1_1") (pintype "passive"))
      (node (ref "C23") (pin "1") (pinfunction "1_1") (pintype "passive"))
      (node (ref "C3") (pin "1") (pinfunction "1_1") (pintype "passive"))
      (node (ref "C39") (pin "1") (pinfunction "1_1") (pintype "passive"))
      (node (ref "C42") (pin "1") (pinfunction "1_1") (pintype "passive"))
      (node (ref "C43") (pin "1") (pinfunction "1_1") (pintype "passive"))
      (node (ref "D0") (pin "A") (pinfunction "A_A") (pintype "passive"))
      (node (ref "D4") (pin "A") (pinfunction "A_A") (pintype "passive"))
      (node (ref "D5") (pin "A") (pinfunction "A_A") (pintype "passive"))
      (node (ref "D6") (pin "A") (pinfunction "A_A") (pintype "passive"))
      (node (ref "J2") (pin "2") (pinfunction "2_2") (pintype "bidirectional"))
      (node (ref "JPDEBUG") (pin "1") (pinfunction "VCC_1") (pintype "bidirectional"))
      (node (ref "R14") (pin "1") (pinfunction "1_1") (pintype "passive"))
      (node (ref "R15") (pin "1") (pinfunction "1_1") (pintype "passive"))
      (node (ref "R2") (pin "1") (pinfunction "1_1") (pintype "passive"))
      (node (ref "R25") (pin "2") (pinfunction "2_2") (pintype "passive"))
      (node (ref "R5") (pin "2") (pinfunction "2_2") (pintype "passive"))
      (node (ref "U1") (pin "1") (pinfunction "PA0/GPIO_EM4WU0/I2C0_SDA#0/LEU0_RX#4/PRS_CH0/TIM0_CC0#0,1,4_1") (pintype "bidirectional"))
      (node (ref "U13") (pin "7") (pinfunction "Z_7") (pintype "bidirectional"))
      (node (ref "U17") (pin "A1") (pinfunction "IN_A1") (pintype "bidirectional"))
      (node (ref "U18") (pin "11") (pinfunction "VCCB_11") (pintype "bidirectional"))
      (node (ref "U2") (pin "1") (pinfunction "VDD_1_1") (pintype "bidirectional"))
      (node (ref "U2") (pin "24") (pinfunction "AVDD_24_24") (pintype "bidirectional"))
      (node (ref "U2") (pin "26") (pinfunction "AVDD_26_26") (pintype "bidirectional"))
      (node (ref "U2") (pin "29") (pinfunction "AVDD_29_29") (pintype "bidirectional"))
      (node (ref "U2") (pin "9") (pinfunction "VDD_9_9") (pintype "bidirectional"))
      (node (ref "U3") (pin "1") (pinfunction "VDD_IO_1") (pintype "bidirectional"))
      (node (ref "U3") (pin "14") (pinfunction "VDD_14") (pintype "bidirectional"))
      (node (ref "U9") (pin "2") (pinfunction "VIN2_2") (pintype "bidirectional"))
      (node (ref "U9") (pin "3") (pinfunction "VIN3_3") (pintype "bidirectional"))
    )
    (net (code "100") (name "VUNREG") (class "Default")
      (node (ref "C18") (pin "1") (pinfunction "1_1") (pintype "passive"))
      (node (ref "C20") (pin "1") (pinfunction "1_1") (pintype "passive"))
      (node (ref "C50") (pin "1") (pinfunction "1_1") (pintype "passive"))
      (node (ref "C9") (pin "1") (pinfunction "1_1") (pintype "passive"))
      (node (ref "J2") (pin "5") (pinfunction "5_5") (pintype "bidirectional"))
      (node (ref "U10") (pin "4") (pinfunction "VCC_4") (pintype "bidirectional"))
      (node (ref "U11") (pin "4") (pinfunction "EN_4") (pintype "bidirectional"))
      (node (ref "U11") (pin "6") (pinfunction "IN_6") (pintype "bidirectional"))
      (node (ref "U12") (pin "8") (pinfunction "VIN_8") (pintype "bidirectional"))
      (node (ref "U14") (pin "4") (pinfunction "S_4") (pintype "passive"))
      (node (ref "U14") (pin "6") (pinfunction "C_6") (pintype "passive"))
      (node (ref "U5") (pin "C5") (pinfunction "VBAT_C5") (pintype "bidirectional"))
    )
    (net (code "101") (name "unconnected-(JPDEBUG-SWO-Pad6)") (class "Default")
      (node (ref "JPDEBUG") (pin "6") (pinfunction "SWO_6") (pintype "bidirectional"))
    )
    (net (code "102") (name "unconnected-(U1A-PA6{slash}ETM_TCLK#3{slash}GPIO_EM4WU1{slash}LEU1_RX#1-Pad7)") (class "Default")
      (node (ref "U1") (pin "7") (pinfunction "PA6/ETM_TCLK#3/GPIO_EM4WU1/LEU1_RX#1_7") (pintype "bidirectional"))
    )
    (net (code "103") (name "unconnected-(U1C-PC2{slash}ACMP0_CH2{slash}DAC0_OUT0ALT{slash}OPAMP_OUT0ALT#2{slash}LES_CH2{slash}TIM0_CDTI0#4{slash}US2_TX-Pad11)") (class "Default")
      (node (ref "U1") (pin "11") (pinfunction "PC2/ACMP0_CH2/DAC0_OUT0ALT/OPAMP_OUT0ALT#2/LES_CH2/TIM0_CDTI0#4/US2_TX_11") (pintype "bidirectional"))
    )
    (net (code "104") (name "unconnected-(U1C-PC3{slash}ACMP0_CH3{slash}DAC0_OUT0ALT{slash}OPAMP_OUT0ALT#3{slash}LES_CH3{slash}TIM0_CDTI1#4{slash}US2_RX-Pad12)") (class "Default")
      (node (ref "U1") (pin "12") (pinfunction "PC3/ACMP0_CH3/DAC0_OUT0ALT/OPAMP_OUT0ALT#3/LES_CH3/TIM0_CDTI1#4/US2_RX_12") (pintype "bidirectional"))
    )
    (net (code "105") (name "unconnected-(U1C-PC4{slash}ACMP0_CH4{slash}DAC0_P0{slash}OPAMP_P0{slash}I2C1_SDA#0{slash}LES_CH4{slash}LETIM0_OUT0#3{slash}PCNT1_S0IN{slash}TIM0_CDTI2#4{slash}US2_CLK-Pad13)") (class "Default")
      (node (ref "U1") (pin "13") (pinfunction "PC4/ACMP0_CH4/DAC0_P0/OPAMP_P0/I2C1_SDA#0/LES_CH4/LETIM0_OUT0#3/PCNT1_S0IN/TIM0_CDTI2#4/US2_CLK_13") (pintype "bidirectional"))
    )
    (net (code "106") (name "unconnected-(U1C-PC5{slash}ACMP0_CH5{slash}DAC0_N0{slash}OPAMP_N0{slash}I2C1_SCL#0{slash}LES_CH5{slash}LETIM0_OUT1#3{slash}PCNT1_S1IN{slash}US2_CS-Pad14)") (class "Default")
      (node (ref "U1") (pin "14") (pinfunction "PC5/ACMP0_CH5/DAC0_N0/OPAMP_N0/I2C1_SCL#0/LES_CH5/LETIM0_OUT1#3/PCNT1_S1IN/US2_CS_14") (pintype "bidirectional"))
    )
    (net (code "107") (name "unconnected-(U1E-PE8{slash}PCNT2_S0IN#1{slash}PRS_CH3#1-Pad56)") (class "Default")
      (node (ref "U1") (pin "56") (pinfunction "PE8/PCNT2_S0IN#1/PRS_CH3#1_56") (pintype "bidirectional"))
    )
    (net (code "108") (name "unconnected-(U1E-PE13{slash}ACMP0_O#0{slash}GPIO_EM4WU5{slash}I2C0_SCL#6{slash}LES_ALTEX7{slash}US0_CS#0{slash}US0_TX#3-Pad61)") (class "Default")
      (node (ref "U1") (pin "61") (pinfunction "PE13/ACMP0_O#0/GPIO_EM4WU5/I2C0_SCL#6/LES_ALTEX7/US0_CS#0/US0_TX#3_61") (pintype "bidirectional"))
    )
    (net (code "109") (name "unconnected-(U1E-PE14{slash}LEU0_TX#2{slash}TIM3_CC0-Pad62)") (class "Default")
      (node (ref "U1") (pin "62") (pinfunction "PE14/LEU0_TX#2/TIM3_CC0_62") (pintype "bidirectional"))
    )
    (net (code "110") (name "unconnected-(U1E-PE15{slash}LEU0_RX#2{slash}TIM3_CC1-Pad63)") (class "Default")
      (node (ref "U1") (pin "63") (pinfunction "PE15/LEU0_RX#2/TIM3_CC1_63") (pintype "bidirectional"))
    )
    (net (code "111") (name "unconnected-(U1F-PF12{slash}USB_ID-Pad53)") (class "Default")
      (node (ref "U1") (pin "53") (pinfunction "PF12/USB_ID_53") (pintype "bidirectional"))
    )
    (net (code "112") (name "unconnected-(U2-ACTIVE-Pad6)") (class "Default")
      (node (ref "U2") (pin "6") (pinfunction "ACTIVE_6") (pintype "bidirectional"))
    )
    (net (code "113") (name "unconnected-(U2-DCC-Pad32)") (class "Default")
      (node (ref "U2") (pin "32") (pinfunction "DCC_32") (pintype "bidirectional"))
    )
    (net (code "114") (name "unconnected-(U2-N{slash}C-Pad15)") (class "Default")
      (node (ref "U2") (pin "15") (pinfunction "N/C_15") (pintype "bidirectional"))
    )
    (net (code "115") (name "unconnected-(U2-RXD-Pad10)") (class "Default")
      (node (ref "U2") (pin "10") (pinfunction "RXD_10") (pintype "bidirectional"))
    )
    (net (code "116") (name "unconnected-(U2-TXD-Pad7)") (class "Default")
      (node (ref "U2") (pin "7") (pinfunction "TXD_7") (pintype "bidirectional"))
    )
    (net (code "117") (name "unconnected-(U2-XL2-Pad4)") (class "Default")
      (node (ref "U2") (pin "4") (pinfunction "XL2_4") (pintype "bidirectional"))
    )
    (net (code "118") (name "unconnected-(U3-ADC1-Pad16)") (class "Default")
      (node (ref "U3") (pin "16") (pinfunction "ADC1_16") (pintype "bidirectional"))
    )
    (net (code "119") (name "unconnected-(U3-ADC2-Pad15)") (class "Default")
      (node (ref "U3") (pin "15") (pinfunction "ADC2_15") (pintype "bidirectional"))
    )
    (net (code "120") (name "unconnected-(U3-ADC3-Pad13)") (class "Default")
      (node (ref "U3") (pin "13") (pinfunction "ADC3_13") (pintype "bidirectional"))
    )
    (net (code "121") (name "unconnected-(U3-INT2-Pad9)") (class "Default")
      (node (ref "U3") (pin "9") (pinfunction "INT2_9") (pintype "bidirectional"))
    )
    (net (code "122") (name "unconnected-(U3-NC2-Pad2)") (class "Default")
      (node (ref "U3") (pin "2") (pinfunction "NC2_2") (pintype "bidirectional"))
    )
    (net (code "123") (name "unconnected-(U3-NC3-Pad3)") (class "Default")
      (node (ref "U3") (pin "3") (pinfunction "NC3_3") (pintype "bidirectional"))
    )
    (net (code "124") (name "unconnected-(U5-GPO-PadE2)") (class "Default")
      (node (ref "U5") (pin "E2") (pinfunction "GPO_E2") (pintype "bidirectional"))
    )
    (net (code "125") (name "unconnected-(U5-INT-PadD3)") (class "Default")
      (node (ref "U5") (pin "D3") (pinfunction "INT_D3") (pintype "bidirectional"))
    )
    (net (code "126") (name "unconnected-(U12-PG-Pad6)") (class "Default")
      (node (ref "U12") (pin "6") (pinfunction "PG_6") (pintype "bidirectional"))
    )
  )
)
